# breakout.net
KiCad netlist of a schematic drawn in EAGLE
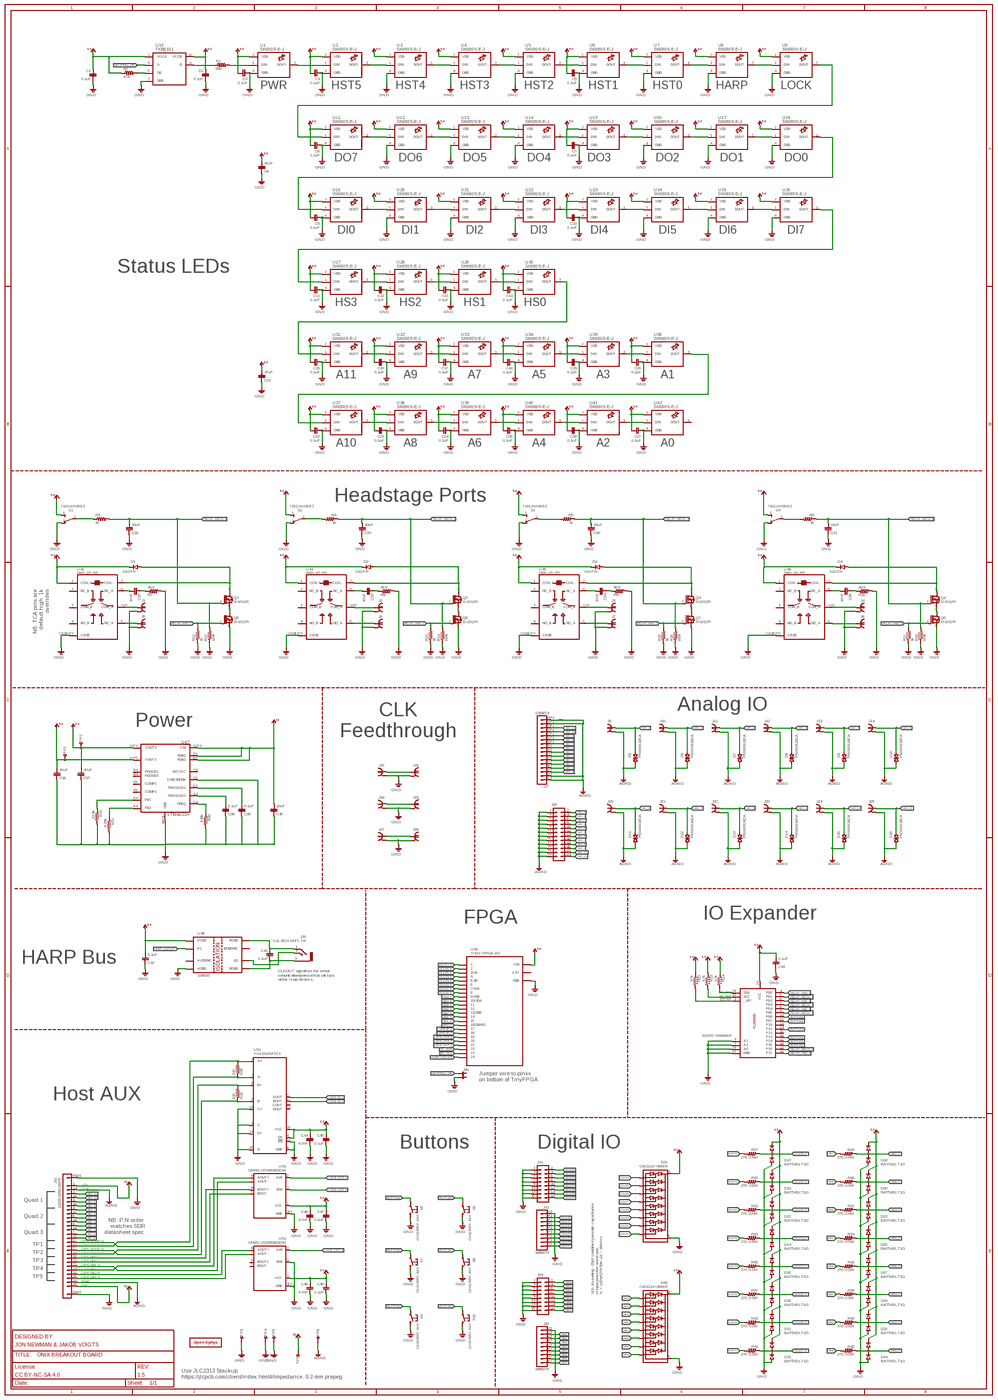
[diagram p0: schematic, sheet 1, overview]
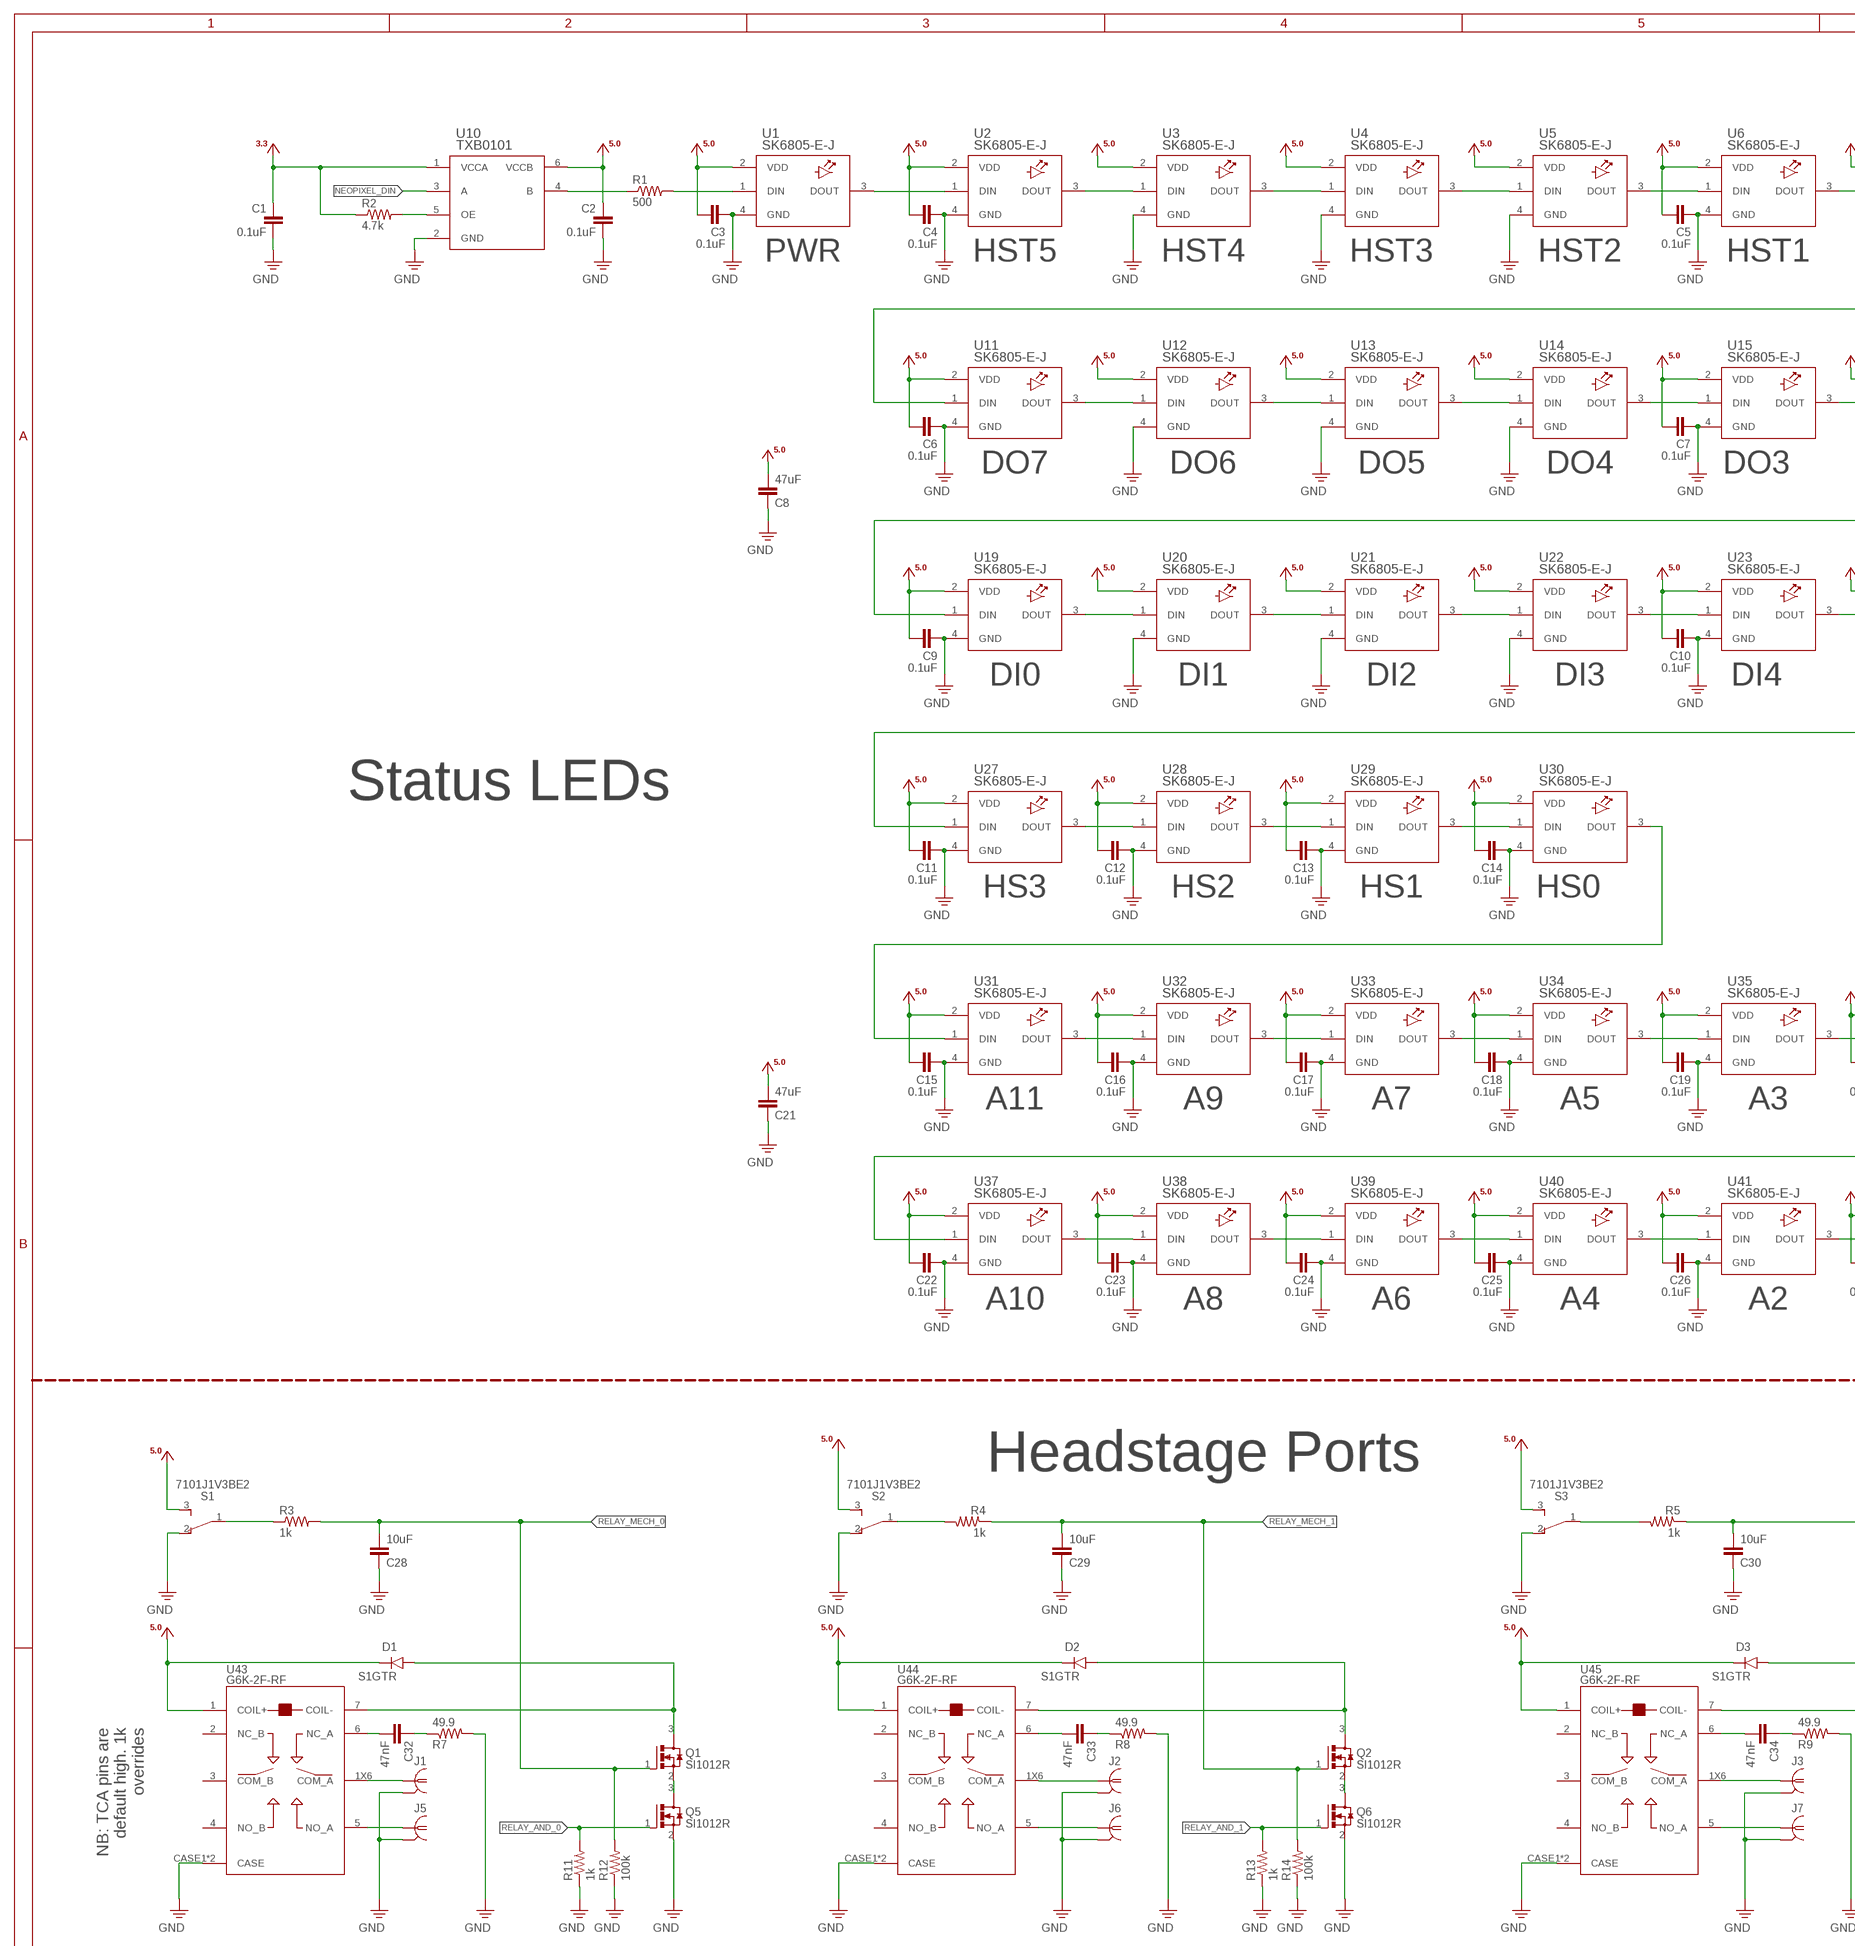
[diagram p1: schematic, sheet 1, part 1 of 4]
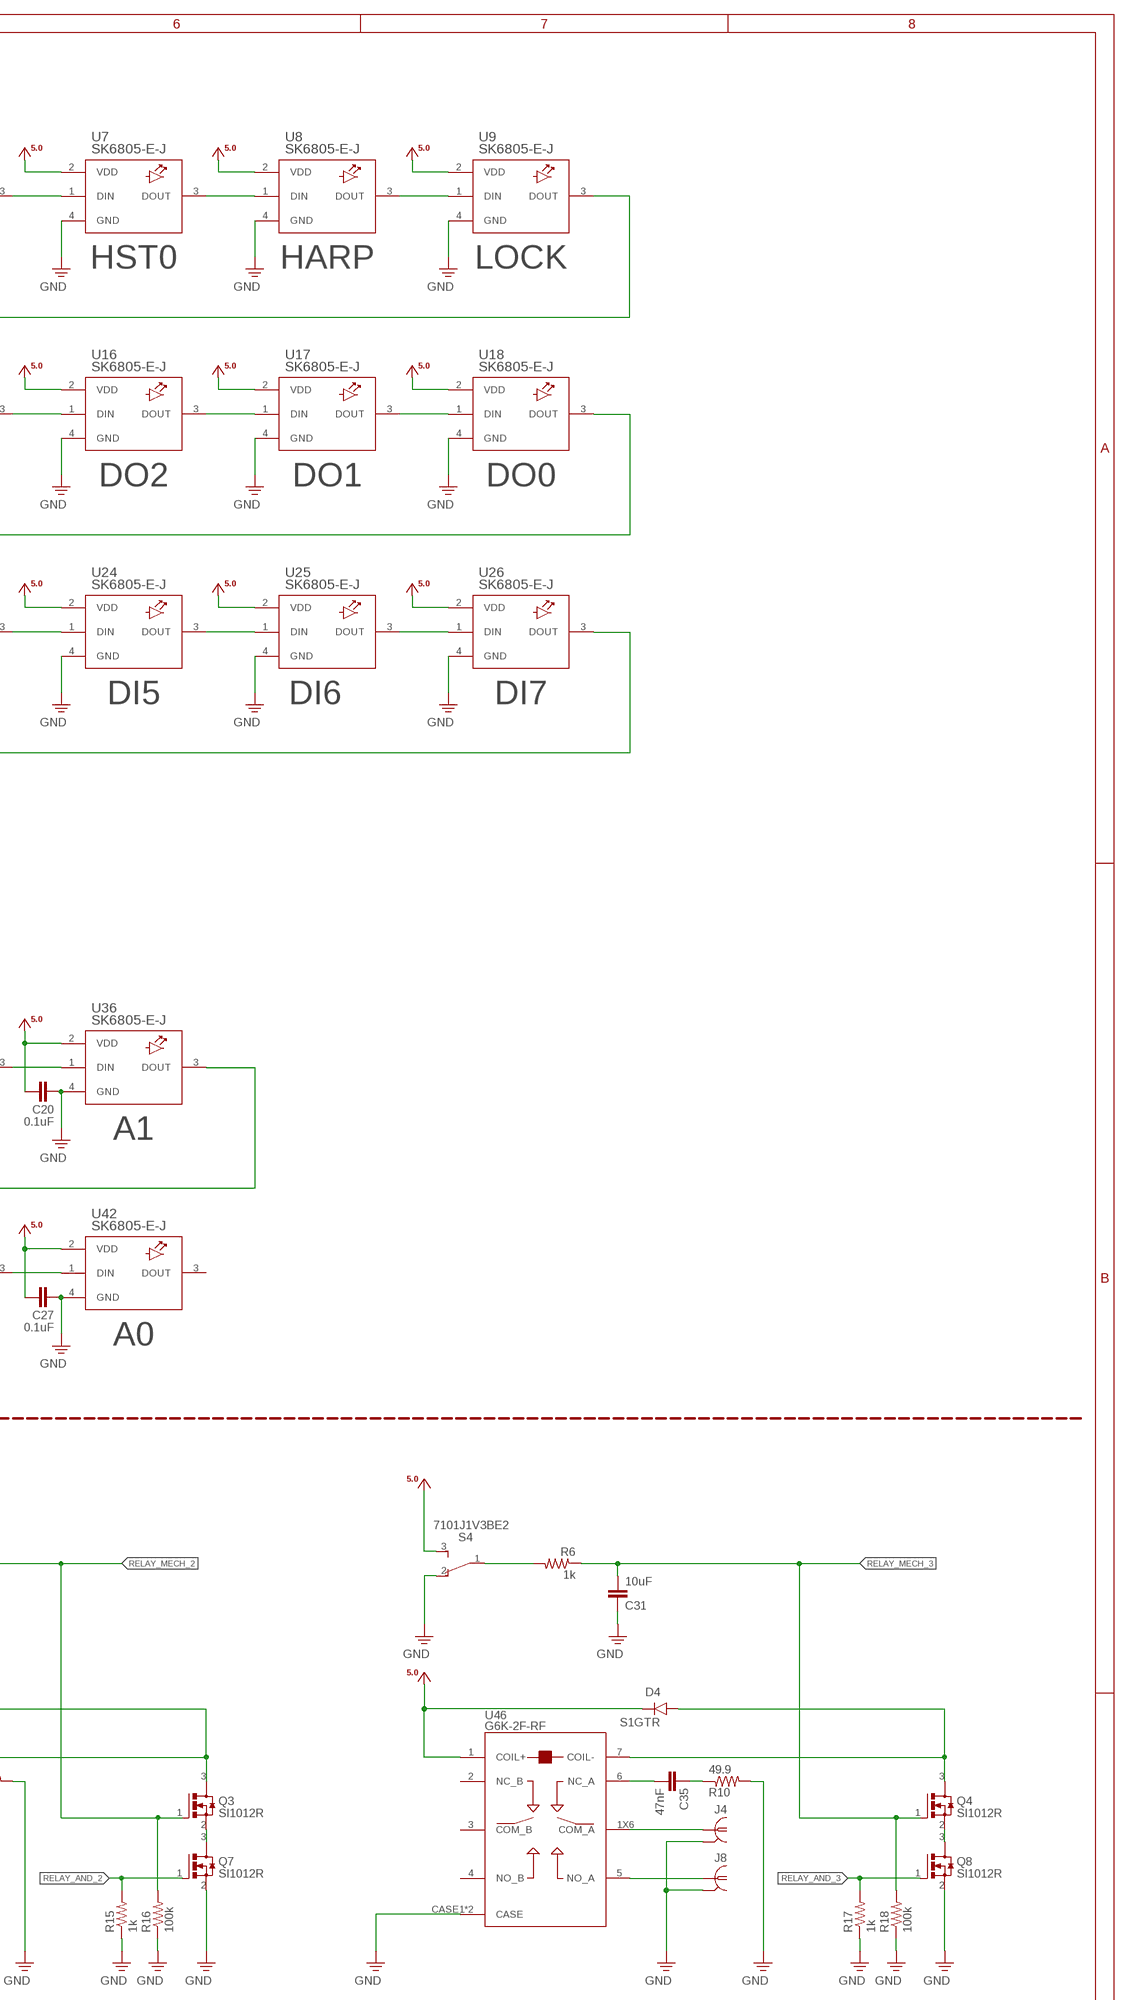
[diagram p2: schematic, sheet 1, part 2 of 4]
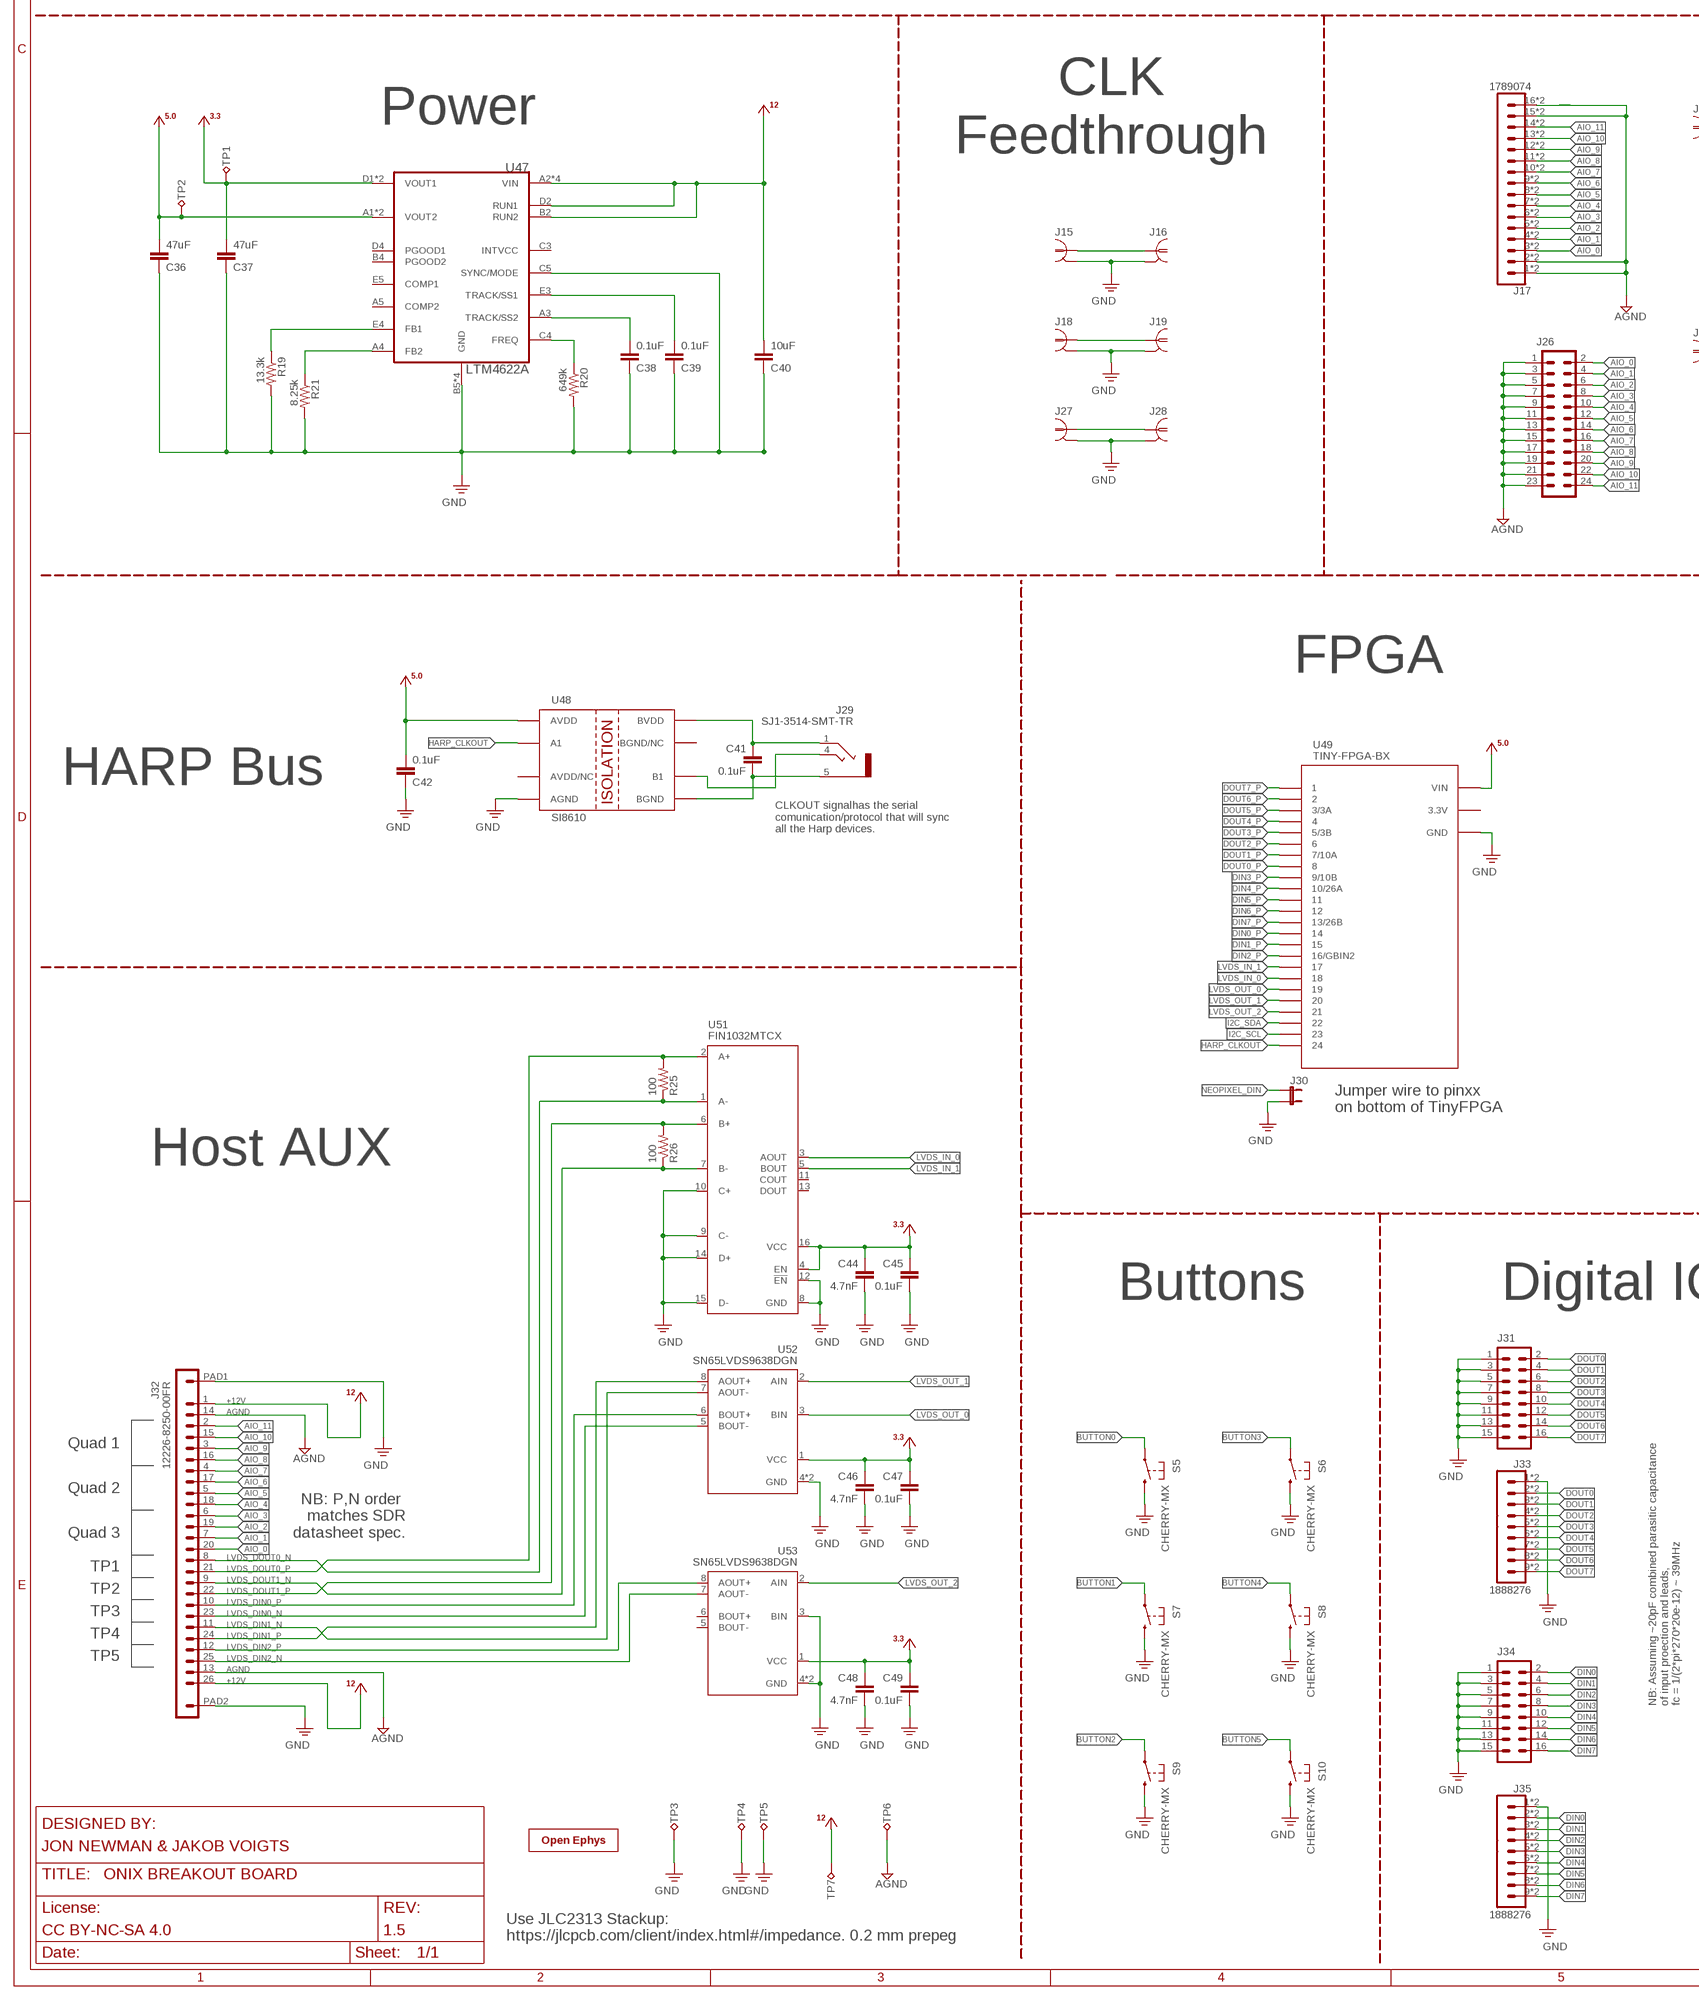
[diagram p3: schematic, sheet 1, part 3 of 4]
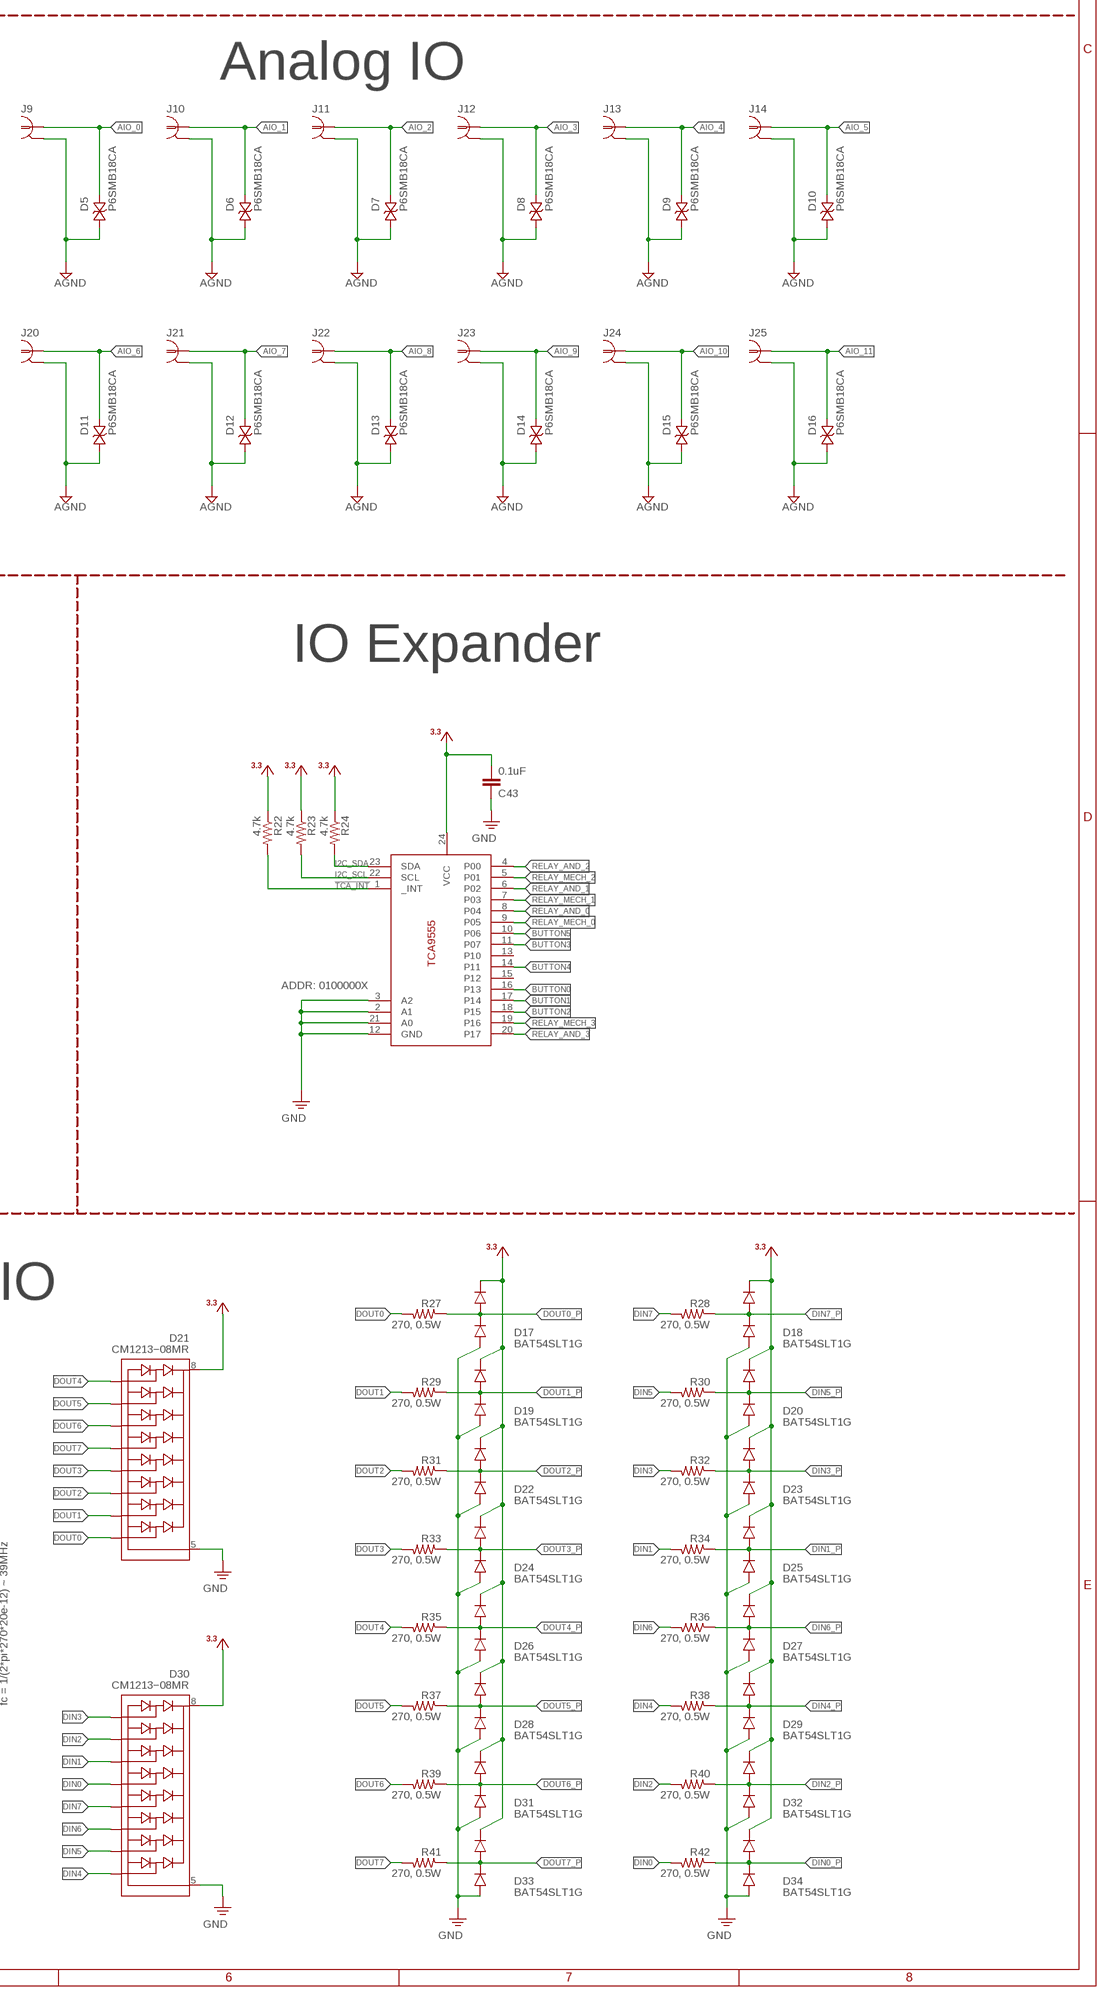
[diagram p4: schematic, sheet 1, part 4 of 4]

(export (version "E")
  (design (tool "Eeschema 10.0.6"))
  (components
    (comp (ref "C1")
      (value "0.1uF")
      (footprint "eagle-import:0402")
      (libsource (lib "eagle-import") (part "C_0402"))
    )
    (comp (ref "C2")
      (value "0.1uF")
      (footprint "eagle-import:0402")
      (libsource (lib "eagle-import") (part "C_0402"))
    )
    (comp (ref "C3")
      (value "0.1uF")
      (footprint "eagle-import:0402")
      (libsource (lib "eagle-import") (part "C_0402"))
    )
    (comp (ref "C4")
      (value "0.1uF")
      (footprint "eagle-import:0402")
      (libsource (lib "eagle-import") (part "C_0402"))
    )
    (comp (ref "C5")
      (value "0.1uF")
      (footprint "eagle-import:0402")
      (libsource (lib "eagle-import") (part "C_0402"))
    )
    (comp (ref "C6")
      (value "0.1uF")
      (footprint "eagle-import:0402")
      (libsource (lib "eagle-import") (part "C_0402"))
    )
    (comp (ref "C7")
      (value "0.1uF")
      (footprint "eagle-import:0402")
      (libsource (lib "eagle-import") (part "C_0402"))
    )
    (comp (ref "C8")
      (value "47uF")
      (footprint "eagle-import:1210")
      (libsource (lib "eagle-import") (part "C_1210"))
    )
    (comp (ref "C9")
      (value "0.1uF")
      (footprint "eagle-import:0402")
      (libsource (lib "eagle-import") (part "C_0402"))
    )
    (comp (ref "C10")
      (value "0.1uF")
      (footprint "eagle-import:0402")
      (libsource (lib "eagle-import") (part "C_0402"))
    )
    (comp (ref "C11")
      (value "0.1uF")
      (footprint "eagle-import:0402")
      (libsource (lib "eagle-import") (part "C_0402"))
    )
    (comp (ref "C12")
      (value "0.1uF")
      (footprint "eagle-import:0402")
      (libsource (lib "eagle-import") (part "C_0402"))
    )
    (comp (ref "C13")
      (value "0.1uF")
      (footprint "eagle-import:0402")
      (libsource (lib "eagle-import") (part "C_0402"))
    )
    (comp (ref "C14")
      (value "0.1uF")
      (footprint "eagle-import:0402")
      (libsource (lib "eagle-import") (part "C_0402"))
    )
    (comp (ref "C15")
      (value "0.1uF")
      (footprint "eagle-import:0402")
      (libsource (lib "eagle-import") (part "C_0402"))
    )
    (comp (ref "C16")
      (value "0.1uF")
      (footprint "eagle-import:0402")
      (libsource (lib "eagle-import") (part "C_0402"))
    )
    (comp (ref "C17")
      (value "0.1uF")
      (footprint "eagle-import:0402")
      (libsource (lib "eagle-import") (part "C_0402"))
    )
    (comp (ref "C18")
      (value "0.1uF")
      (footprint "eagle-import:0402")
      (libsource (lib "eagle-import") (part "C_0402"))
    )
    (comp (ref "C19")
      (value "0.1uF")
      (footprint "eagle-import:0402")
      (libsource (lib "eagle-import") (part "C_0402"))
    )
    (comp (ref "C20")
      (value "0.1uF")
      (footprint "eagle-import:0402")
      (libsource (lib "eagle-import") (part "C_0402"))
    )
    (comp (ref "C21")
      (value "47uF")
      (footprint "eagle-import:1210")
      (libsource (lib "eagle-import") (part "C_1210"))
    )
    (comp (ref "C22")
      (value "0.1uF")
      (footprint "eagle-import:0402")
      (libsource (lib "eagle-import") (part "C_0402"))
    )
    (comp (ref "C23")
      (value "0.1uF")
      (footprint "eagle-import:0402")
      (libsource (lib "eagle-import") (part "C_0402"))
    )
    (comp (ref "C24")
      (value "0.1uF")
      (footprint "eagle-import:0402")
      (libsource (lib "eagle-import") (part "C_0402"))
    )
    (comp (ref "C25")
      (value "0.1uF")
      (footprint "eagle-import:0402")
      (libsource (lib "eagle-import") (part "C_0402"))
    )
    (comp (ref "C26")
      (value "0.1uF")
      (footprint "eagle-import:0402")
      (libsource (lib "eagle-import") (part "C_0402"))
    )
    (comp (ref "C27")
      (value "0.1uF")
      (footprint "eagle-import:0402")
      (libsource (lib "eagle-import") (part "C_0402"))
    )
    (comp (ref "C28")
      (value "10uF")
      (footprint "eagle-import:0805")
      (fields (field (name "PARTNO") "C2012X5R1Cxxxxxxx"))
      (libsource (lib "eagle-import") (part "C_0805"))
    )
    (comp (ref "C29")
      (value "10uF")
      (footprint "eagle-import:0805")
      (fields (field (name "PARTNO") "C2012X5R1Cxxxxxxx"))
      (libsource (lib "eagle-import") (part "C_0805"))
    )
    (comp (ref "C30")
      (value "10uF")
      (footprint "eagle-import:0805")
      (fields (field (name "PARTNO") "C2012X5R1Cxxxxxxx"))
      (libsource (lib "eagle-import") (part "C_0805"))
    )
    (comp (ref "C31")
      (value "10uF")
      (footprint "eagle-import:0805")
      (fields (field (name "PARTNO") "C2012X5R1Cxxxxxxx"))
      (libsource (lib "eagle-import") (part "C_0805"))
    )
    (comp (ref "C32")
      (value "47nF")
      (footprint "eagle-import:0402")
      (libsource (lib "eagle-import") (part "C_0402"))
    )
    (comp (ref "C33")
      (value "47nF")
      (footprint "eagle-import:0402")
      (libsource (lib "eagle-import") (part "C_0402"))
    )
    (comp (ref "C34")
      (value "47nF")
      (footprint "eagle-import:0402")
      (libsource (lib "eagle-import") (part "C_0402"))
    )
    (comp (ref "C35")
      (value "47nF")
      (footprint "eagle-import:0402")
      (libsource (lib "eagle-import") (part "C_0402"))
    )
    (comp (ref "C36")
      (value "47uF")
      (footprint "eagle-import:1210")
      (libsource (lib "eagle-import") (part "C_1210"))
    )
    (comp (ref "C37")
      (value "47uF")
      (footprint "eagle-import:1210")
      (libsource (lib "eagle-import") (part "C_1210"))
    )
    (comp (ref "C38")
      (value "0.1uF")
      (footprint "eagle-import:0402")
      (libsource (lib "eagle-import") (part "C_0402"))
    )
    (comp (ref "C39")
      (value "0.1uF")
      (footprint "eagle-import:0402")
      (libsource (lib "eagle-import") (part "C_0402"))
    )
    (comp (ref "C40")
      (value "10uF")
      (footprint "eagle-import:0805")
      (fields (field (name "PARTNO") "C2012X5R1Cxxxxxxx"))
      (libsource (lib "eagle-import") (part "C_0805"))
    )
    (comp (ref "C41")
      (value "0.1uF")
      (footprint "eagle-import:0402")
      (libsource (lib "eagle-import") (part "C_0402"))
    )
    (comp (ref "C42")
      (value "0.1uF")
      (footprint "eagle-import:0402")
      (libsource (lib "eagle-import") (part "C_0402"))
    )
    (comp (ref "C43")
      (value "0.1uF")
      (footprint "eagle-import:0402")
      (libsource (lib "eagle-import") (part "C_0402"))
    )
    (comp (ref "C44")
      (value "4.7nF")
      (footprint "eagle-import:0402")
      (libsource (lib "eagle-import") (part "C_0402"))
    )
    (comp (ref "C45")
      (value "0.1uF")
      (footprint "eagle-import:0402")
      (libsource (lib "eagle-import") (part "C_0402"))
    )
    (comp (ref "C46")
      (value "4.7nF")
      (footprint "eagle-import:0402")
      (libsource (lib "eagle-import") (part "C_0402"))
    )
    (comp (ref "C47")
      (value "0.1uF")
      (footprint "eagle-import:0402")
      (libsource (lib "eagle-import") (part "C_0402"))
    )
    (comp (ref "C48")
      (value "4.7nF")
      (footprint "eagle-import:0402")
      (libsource (lib "eagle-import") (part "C_0402"))
    )
    (comp (ref "C49")
      (value "0.1uF")
      (footprint "eagle-import:0402")
      (libsource (lib "eagle-import") (part "C_0402"))
    )
    (comp (ref "D1")
      (value "S1GTR")
      (footprint "eagle-import:SMA-DO214AC")
      (libsource (lib "eagle-import") (part "DIODE_S1B-13-F"))
    )
    (comp (ref "D2")
      (value "S1GTR")
      (footprint "eagle-import:SMA-DO214AC")
      (libsource (lib "eagle-import") (part "DIODE_S1B-13-F"))
    )
    (comp (ref "D3")
      (value "S1GTR")
      (footprint "eagle-import:SMA-DO214AC")
      (libsource (lib "eagle-import") (part "DIODE_S1B-13-F"))
    )
    (comp (ref "D4")
      (value "S1GTR")
      (footprint "eagle-import:SMA-DO214AC")
      (libsource (lib "eagle-import") (part "DIODE_S1B-13-F"))
    )
    (comp (ref "D5")
      (value "P6SMB18CA")
      (footprint "eagle-import:SMA-DO214AC")
      (libsource (lib "eagle-import") (part "TVS-DIODE-BI_DO214"))
    )
    (comp (ref "D6")
      (value "P6SMB18CA")
      (footprint "eagle-import:SMA-DO214AC")
      (libsource (lib "eagle-import") (part "TVS-DIODE-BI_DO214"))
    )
    (comp (ref "D7")
      (value "P6SMB18CA")
      (footprint "eagle-import:SMA-DO214AC")
      (libsource (lib "eagle-import") (part "TVS-DIODE-BI_DO214"))
    )
    (comp (ref "D8")
      (value "P6SMB18CA")
      (footprint "eagle-import:SMA-DO214AC")
      (libsource (lib "eagle-import") (part "TVS-DIODE-BI_DO214"))
    )
    (comp (ref "D9")
      (value "P6SMB18CA")
      (footprint "eagle-import:SMA-DO214AC")
      (libsource (lib "eagle-import") (part "TVS-DIODE-BI_DO214"))
    )
    (comp (ref "D10")
      (value "P6SMB18CA")
      (footprint "eagle-import:SMA-DO214AC")
      (libsource (lib "eagle-import") (part "TVS-DIODE-BI_DO214"))
    )
    (comp (ref "D11")
      (value "P6SMB18CA")
      (footprint "eagle-import:SMA-DO214AC")
      (libsource (lib "eagle-import") (part "TVS-DIODE-BI_DO214"))
    )
    (comp (ref "D12")
      (value "P6SMB18CA")
      (footprint "eagle-import:SMA-DO214AC")
      (libsource (lib "eagle-import") (part "TVS-DIODE-BI_DO214"))
    )
    (comp (ref "D13")
      (value "P6SMB18CA")
      (footprint "eagle-import:SMA-DO214AC")
      (libsource (lib "eagle-import") (part "TVS-DIODE-BI_DO214"))
    )
    (comp (ref "D14")
      (value "P6SMB18CA")
      (footprint "eagle-import:SMA-DO214AC")
      (libsource (lib "eagle-import") (part "TVS-DIODE-BI_DO214"))
    )
    (comp (ref "D15")
      (value "P6SMB18CA")
      (footprint "eagle-import:SMA-DO214AC")
      (libsource (lib "eagle-import") (part "TVS-DIODE-BI_DO214"))
    )
    (comp (ref "D16")
      (value "P6SMB18CA")
      (footprint "eagle-import:SMA-DO214AC")
      (libsource (lib "eagle-import") (part "TVS-DIODE-BI_DO214"))
    )
    (comp (ref "D17")
      (value "BAT54SLT1G")
      (footprint "eagle-import:SOT23")
      (libsource (lib "eagle-import") (part "DIODE2_SOT23"))
    )
    (comp (ref "D18")
      (value "BAT54SLT1G")
      (footprint "eagle-import:SOT23")
      (libsource (lib "eagle-import") (part "DIODE2_SOT23"))
    )
    (comp (ref "D19")
      (value "BAT54SLT1G")
      (footprint "eagle-import:SOT23")
      (libsource (lib "eagle-import") (part "DIODE2_SOT23"))
    )
    (comp (ref "D20")
      (value "BAT54SLT1G")
      (footprint "eagle-import:SOT23")
      (libsource (lib "eagle-import") (part "DIODE2_SOT23"))
    )
    (comp (ref "D21")
      (value "CM1213−08MR")
      (footprint "eagle-import:MSOP-10-3X3")
      (libsource (lib "eagle-import") (part "TVS-DIODE-BI-8_MSOP"))
    )
    (comp (ref "D22")
      (value "BAT54SLT1G")
      (footprint "eagle-import:SOT23")
      (libsource (lib "eagle-import") (part "DIODE2_SOT23"))
    )
    (comp (ref "D23")
      (value "BAT54SLT1G")
      (footprint "eagle-import:SOT23")
      (libsource (lib "eagle-import") (part "DIODE2_SOT23"))
    )
    (comp (ref "D24")
      (value "BAT54SLT1G")
      (footprint "eagle-import:SOT23")
      (libsource (lib "eagle-import") (part "DIODE2_SOT23"))
    )
    (comp (ref "D25")
      (value "BAT54SLT1G")
      (footprint "eagle-import:SOT23")
      (libsource (lib "eagle-import") (part "DIODE2_SOT23"))
    )
    (comp (ref "D26")
      (value "BAT54SLT1G")
      (footprint "eagle-import:SOT23")
      (libsource (lib "eagle-import") (part "DIODE2_SOT23"))
    )
    (comp (ref "D27")
      (value "BAT54SLT1G")
      (footprint "eagle-import:SOT23")
      (libsource (lib "eagle-import") (part "DIODE2_SOT23"))
    )
    (comp (ref "D28")
      (value "BAT54SLT1G")
      (footprint "eagle-import:SOT23")
      (libsource (lib "eagle-import") (part "DIODE2_SOT23"))
    )
    (comp (ref "D29")
      (value "BAT54SLT1G")
      (footprint "eagle-import:SOT23")
      (libsource (lib "eagle-import") (part "DIODE2_SOT23"))
    )
    (comp (ref "D30")
      (value "CM1213−08MR")
      (footprint "eagle-import:MSOP-10-3X3")
      (libsource (lib "eagle-import") (part "TVS-DIODE-BI-8_MSOP"))
    )
    (comp (ref "D31")
      (value "BAT54SLT1G")
      (footprint "eagle-import:SOT23")
      (libsource (lib "eagle-import") (part "DIODE2_SOT23"))
    )
    (comp (ref "D32")
      (value "BAT54SLT1G")
      (footprint "eagle-import:SOT23")
      (libsource (lib "eagle-import") (part "DIODE2_SOT23"))
    )
    (comp (ref "D33")
      (value "BAT54SLT1G")
      (footprint "eagle-import:SOT23")
      (libsource (lib "eagle-import") (part "DIODE2_SOT23"))
    )
    (comp (ref "D34")
      (value "BAT54SLT1G")
      (footprint "eagle-import:SOT23")
      (libsource (lib "eagle-import") (part "DIODE2_SOT23"))
    )
    (comp (ref "J1")
      (value "COAX_SMA-VERT")
      (footprint "eagle-import:SMA_JACK_142-0701-201")
      (libsource (lib "eagle-import") (part "COAX_SMA-VERT"))
    )
    (comp (ref "J2")
      (value "COAX_SMA-VERT")
      (footprint "eagle-import:SMA_JACK_142-0701-201")
      (libsource (lib "eagle-import") (part "COAX_SMA-VERT"))
    )
    (comp (ref "J3")
      (value "COAX_SMA-VERT")
      (footprint "eagle-import:SMA_JACK_142-0701-201")
      (libsource (lib "eagle-import") (part "COAX_SMA-VERT"))
    )
    (comp (ref "J4")
      (value "COAX_SMA-VERT")
      (footprint "eagle-import:SMA_JACK_142-0701-201")
      (libsource (lib "eagle-import") (part "COAX_SMA-VERT"))
    )
    (comp (ref "J5")
      (value "COAX_MMCX-THRU")
      (footprint "eagle-import:MMCX-THRU")
      (libsource (lib "eagle-import") (part "COAX_MMCX-THRU"))
    )
    (comp (ref "J6")
      (value "COAX_MMCX-THRU")
      (footprint "eagle-import:MMCX-THRU")
      (libsource (lib "eagle-import") (part "COAX_MMCX-THRU"))
    )
    (comp (ref "J7")
      (value "COAX_MMCX-THRU")
      (footprint "eagle-import:MMCX-THRU")
      (libsource (lib "eagle-import") (part "COAX_MMCX-THRU"))
    )
    (comp (ref "J8")
      (value "COAX_MMCX-THRU")
      (footprint "eagle-import:MMCX-THRU")
      (libsource (lib "eagle-import") (part "COAX_MMCX-THRU"))
    )
    (comp (ref "J9")
      (value "COAX_0731010360")
      (footprint "eagle-import:0731010360")
      (libsource (lib "eagle-import") (part "COAX_0731010360"))
    )
    (comp (ref "J10")
      (value "COAX_0731010360")
      (footprint "eagle-import:0731010360")
      (libsource (lib "eagle-import") (part "COAX_0731010360"))
    )
    (comp (ref "J11")
      (value "COAX_0731010360")
      (footprint "eagle-import:0731010360")
      (libsource (lib "eagle-import") (part "COAX_0731010360"))
    )
    (comp (ref "J12")
      (value "COAX_0731010360")
      (footprint "eagle-import:0731010360")
      (libsource (lib "eagle-import") (part "COAX_0731010360"))
    )
    (comp (ref "J13")
      (value "COAX_0731010360")
      (footprint "eagle-import:0731010360")
      (libsource (lib "eagle-import") (part "COAX_0731010360"))
    )
    (comp (ref "J14")
      (value "COAX_0731010360")
      (footprint "eagle-import:0731010360")
      (libsource (lib "eagle-import") (part "COAX_0731010360"))
    )
    (comp (ref "J15")
      (value "COAX_MMCX-THRU")
      (footprint "eagle-import:MMCX-THRU")
      (libsource (lib "eagle-import") (part "COAX_MMCX-THRU"))
    )
    (comp (ref "J16")
      (value "COAX_SMA-VERT")
      (footprint "eagle-import:SMA_JACK_142-0701-201")
      (libsource (lib "eagle-import") (part "COAX_SMA-VERT"))
    )
    (comp (ref "J17")
      (value "1789074")
      (footprint "eagle-import:SCREW16-2")
      (libsource (lib "eagle-import") (part "PINHD-1X16"))
    )
    (comp (ref "J18")
      (value "COAX_MMCX-THRU")
      (footprint "eagle-import:MMCX-THRU")
      (libsource (lib "eagle-import") (part "COAX_MMCX-THRU"))
    )
    (comp (ref "J19")
      (value "COAX_SMA-VERT")
      (footprint "eagle-import:SMA_JACK_142-0701-201")
      (libsource (lib "eagle-import") (part "COAX_SMA-VERT"))
    )
    (comp (ref "J20")
      (value "COAX_0731010360")
      (footprint "eagle-import:0731010360")
      (libsource (lib "eagle-import") (part "COAX_0731010360"))
    )
    (comp (ref "J21")
      (value "COAX_0731010360")
      (footprint "eagle-import:0731010360")
      (libsource (lib "eagle-import") (part "COAX_0731010360"))
    )
    (comp (ref "J22")
      (value "COAX_0731010360")
      (footprint "eagle-import:0731010360")
      (libsource (lib "eagle-import") (part "COAX_0731010360"))
    )
    (comp (ref "J23")
      (value "COAX_0731010360")
      (footprint "eagle-import:0731010360")
      (libsource (lib "eagle-import") (part "COAX_0731010360"))
    )
    (comp (ref "J24")
      (value "COAX_0731010360")
      (footprint "eagle-import:0731010360")
      (libsource (lib "eagle-import") (part "COAX_0731010360"))
    )
    (comp (ref "J25")
      (value "COAX_0731010360")
      (footprint "eagle-import:0731010360")
      (libsource (lib "eagle-import") (part "COAX_0731010360"))
    )
    (comp (ref "J26")
      (value "69168-124HLF")
      (footprint "eagle-import:2X12-BIG")
      (libsource (lib "eagle-import") (part "PINHD-2X12_0.1{dblquote}"))
    )
    (comp (ref "J27")
      (value "COAX_MMCX-THRU")
      (footprint "eagle-import:MMCX-THRU")
      (libsource (lib "eagle-import") (part "COAX_MMCX-THRU"))
    )
    (comp (ref "J28")
      (value "COAX_SMA-VERT")
      (footprint "eagle-import:SMA_JACK_142-0701-201")
      (libsource (lib "eagle-import") (part "COAX_SMA-VERT"))
    )
    (comp (ref "J29")
      (value "SJ1-3514-SMT-TR")
      (footprint "eagle-import:35RASMT2BHNTRX")
      (libsource (lib "eagle-import") (part "STEREO_JACK"))
    )
    (comp (ref "J30")
      (value "JP2E_THRU-HOLE")
      (footprint "eagle-import:JP2")
      (libsource (lib "eagle-import") (part "JP2E_THRU-HOLE"))
    )
    (comp (ref "J31")
      (value "69168-116HLF")
      (footprint "eagle-import:2X08-BIG")
      (libsource (lib "eagle-import") (part "PINHD-2X8_THRU"))
    )
    (comp (ref "J32")
      (value "12226-8250-00FR")
      (footprint "eagle-import:12226-82X0-00XX")
      (libsource (lib "eagle-import") (part "PINHD-1X26_122"))
    )
    (comp (ref "J33")
      (value "1888276")
      (footprint "eagle-import:SCREW9-2")
      (libsource (lib "eagle-import") (part "PINHD-1X9_SCREW2"))
    )
    (comp (ref "J34")
      (value "69168-116HLF")
      (footprint "eagle-import:2X08-BIG")
      (libsource (lib "eagle-import") (part "PINHD-2X8_THRU"))
    )
    (comp (ref "J35")
      (value "1888276")
      (footprint "eagle-import:SCREW9-2")
      (libsource (lib "eagle-import") (part "PINHD-1X9_SCREW2"))
    )
    (comp (ref "Q1")
      (value "SI1012R")
      (footprint "eagle-import:SC75")
      (libsource (lib "eagle-import") (part "N-MOSFET_SC75-GSD"))
    )
    (comp (ref "Q2")
      (value "SI1012R")
      (footprint "eagle-import:SC75")
      (libsource (lib "eagle-import") (part "N-MOSFET_SC75-GSD"))
    )
    (comp (ref "Q3")
      (value "SI1012R")
      (footprint "eagle-import:SC75")
      (libsource (lib "eagle-import") (part "N-MOSFET_SC75-GSD"))
    )
    (comp (ref "Q4")
      (value "SI1012R")
      (footprint "eagle-import:SC75")
      (libsource (lib "eagle-import") (part "N-MOSFET_SC75-GSD"))
    )
    (comp (ref "Q5")
      (value "SI1012R")
      (footprint "eagle-import:SC75")
      (libsource (lib "eagle-import") (part "N-MOSFET_SC75-GSD"))
    )
    (comp (ref "Q6")
      (value "SI1012R")
      (footprint "eagle-import:SC75")
      (libsource (lib "eagle-import") (part "N-MOSFET_SC75-GSD"))
    )
    (comp (ref "Q7")
      (value "SI1012R")
      (footprint "eagle-import:SC75")
      (libsource (lib "eagle-import") (part "N-MOSFET_SC75-GSD"))
    )
    (comp (ref "Q8")
      (value "SI1012R")
      (footprint "eagle-import:SC75")
      (libsource (lib "eagle-import") (part "N-MOSFET_SC75-GSD"))
    )
    (comp (ref "R1")
      (value "500")
      (footprint "eagle-import:0402")
      (libsource (lib "eagle-import") (part "R_0402"))
    )
    (comp (ref "R2")
      (value "4.7k")
      (footprint "eagle-import:0402")
      (libsource (lib "eagle-import") (part "R_0402"))
    )
    (comp (ref "R3")
      (value "1k")
      (footprint "eagle-import:0402")
      (libsource (lib "eagle-import") (part "R_0402"))
    )
    (comp (ref "R4")
      (value "1k")
      (footprint "eagle-import:0402")
      (libsource (lib "eagle-import") (part "R_0402"))
    )
    (comp (ref "R5")
      (value "1k")
      (footprint "eagle-import:0402")
      (libsource (lib "eagle-import") (part "R_0402"))
    )
    (comp (ref "R6")
      (value "1k")
      (footprint "eagle-import:0402")
      (libsource (lib "eagle-import") (part "R_0402"))
    )
    (comp (ref "R7")
      (value "49.9")
      (footprint "eagle-import:0402")
      (libsource (lib "eagle-import") (part "R_0402"))
    )
    (comp (ref "R8")
      (value "49.9")
      (footprint "eagle-import:0402")
      (libsource (lib "eagle-import") (part "R_0402"))
    )
    (comp (ref "R9")
      (value "49.9")
      (footprint "eagle-import:0402")
      (libsource (lib "eagle-import") (part "R_0402"))
    )
    (comp (ref "R10")
      (value "49.9")
      (footprint "eagle-import:0402")
      (libsource (lib "eagle-import") (part "R_0402"))
    )
    (comp (ref "R11")
      (value "1k")
      (footprint "eagle-import:0402")
      (libsource (lib "eagle-import") (part "R_0402"))
    )
    (comp (ref "R12")
      (value "100k")
      (footprint "eagle-import:0402")
      (libsource (lib "eagle-import") (part "R_0402"))
    )
    (comp (ref "R13")
      (value "1k")
      (footprint "eagle-import:0402")
      (libsource (lib "eagle-import") (part "R_0402"))
    )
    (comp (ref "R14")
      (value "100k")
      (footprint "eagle-import:0402")
      (libsource (lib "eagle-import") (part "R_0402"))
    )
    (comp (ref "R15")
      (value "1k")
      (footprint "eagle-import:0402")
      (libsource (lib "eagle-import") (part "R_0402"))
    )
    (comp (ref "R16")
      (value "100k")
      (footprint "eagle-import:0402")
      (libsource (lib "eagle-import") (part "R_0402"))
    )
    (comp (ref "R17")
      (value "1k")
      (footprint "eagle-import:0402")
      (libsource (lib "eagle-import") (part "R_0402"))
    )
    (comp (ref "R18")
      (value "100k")
      (footprint "eagle-import:0402")
      (libsource (lib "eagle-import") (part "R_0402"))
    )
    (comp (ref "R19")
      (value "13.3k")
      (footprint "eagle-import:0402")
      (libsource (lib "eagle-import") (part "R_0402"))
    )
    (comp (ref "R20")
      (value "649k")
      (footprint "eagle-import:0402")
      (libsource (lib "eagle-import") (part "R_0402"))
    )
    (comp (ref "R21")
      (value "8.25k")
      (footprint "eagle-import:0402")
      (libsource (lib "eagle-import") (part "R_0402"))
    )
    (comp (ref "R22")
      (value "4.7k")
      (footprint "eagle-import:0402")
      (libsource (lib "eagle-import") (part "R_0402"))
    )
    (comp (ref "R23")
      (value "4.7k")
      (footprint "eagle-import:0402")
      (libsource (lib "eagle-import") (part "R_0402"))
    )
    (comp (ref "R24")
      (value "4.7k")
      (footprint "eagle-import:0402")
      (libsource (lib "eagle-import") (part "R_0402"))
    )
    (comp (ref "R25")
      (value "100")
      (footprint "eagle-import:0402")
      (libsource (lib "eagle-import") (part "R_0402"))
    )
    (comp (ref "R26")
      (value "100")
      (footprint "eagle-import:0402")
      (libsource (lib "eagle-import") (part "R_0402"))
    )
    (comp (ref "R27")
      (value "270, 0.5W")
      (footprint "eagle-import:0805")
      (libsource (lib "eagle-import") (part "R_0805"))
    )
    (comp (ref "R28")
      (value "270, 0.5W")
      (footprint "eagle-import:0805")
      (libsource (lib "eagle-import") (part "R_0805"))
    )
    (comp (ref "R29")
      (value "270, 0.5W")
      (footprint "eagle-import:0805")
      (libsource (lib "eagle-import") (part "R_0805"))
    )
    (comp (ref "R30")
      (value "270, 0.5W")
      (footprint "eagle-import:0805")
      (libsource (lib "eagle-import") (part "R_0805"))
    )
    (comp (ref "R31")
      (value "270, 0.5W")
      (footprint "eagle-import:0805")
      (libsource (lib "eagle-import") (part "R_0805"))
    )
    (comp (ref "R32")
      (value "270, 0.5W")
      (footprint "eagle-import:0805")
      (libsource (lib "eagle-import") (part "R_0805"))
    )
    (comp (ref "R33")
      (value "270, 0.5W")
      (footprint "eagle-import:0805")
      (libsource (lib "eagle-import") (part "R_0805"))
    )
    (comp (ref "R34")
      (value "270, 0.5W")
      (footprint "eagle-import:0805")
      (libsource (lib "eagle-import") (part "R_0805"))
    )
    (comp (ref "R35")
      (value "270, 0.5W")
      (footprint "eagle-import:0805")
      (libsource (lib "eagle-import") (part "R_0805"))
    )
    (comp (ref "R36")
      (value "270, 0.5W")
      (footprint "eagle-import:0805")
      (libsource (lib "eagle-import") (part "R_0805"))
    )
    (comp (ref "R37")
      (value "270, 0.5W")
      (footprint "eagle-import:0805")
      (libsource (lib "eagle-import") (part "R_0805"))
    )
    (comp (ref "R38")
      (value "270, 0.5W")
      (footprint "eagle-import:0805")
      (libsource (lib "eagle-import") (part "R_0805"))
    )
    (comp (ref "R39")
      (value "270, 0.5W")
      (footprint "eagle-import:0805")
      (libsource (lib "eagle-import") (part "R_0805"))
    )
    (comp (ref "R40")
      (value "270, 0.5W")
      (footprint "eagle-import:0805")
      (libsource (lib "eagle-import") (part "R_0805"))
    )
    (comp (ref "R41")
      (value "270, 0.5W")
      (footprint "eagle-import:0805")
      (libsource (lib "eagle-import") (part "R_0805"))
    )
    (comp (ref "R42")
      (value "270, 0.5W")
      (footprint "eagle-import:0805")
      (libsource (lib "eagle-import") (part "R_0805"))
    )
    (comp (ref "S1")
      (value "7101J1V3BE2")
      (footprint "eagle-import:CK_7101J1V3QE2")
      (libsource (lib "eagle-import") (part "SPDT_CK-710"))
    )
    (comp (ref "S2")
      (value "7101J1V3BE2")
      (footprint "eagle-import:CK_7101J1V3QE2")
      (libsource (lib "eagle-import") (part "SPDT_CK-710"))
    )
    (comp (ref "S3")
      (value "7101J1V3BE2")
      (footprint "eagle-import:CK_7101J1V3QE2")
      (libsource (lib "eagle-import") (part "SPDT_CK-710"))
    )
    (comp (ref "S4")
      (value "7101J1V3BE2")
      (footprint "eagle-import:CK_7101J1V3QE2")
      (libsource (lib "eagle-import") (part "SPDT_CK-710"))
    )
    (comp (ref "S5")
      (value "CHERRY-MX")
      (footprint "eagle-import:CHERRY-MX")
      (libsource (lib "eagle-import") (part "SPST_TACT2_CHERRY-MX"))
    )
    (comp (ref "S6")
      (value "CHERRY-MX")
      (footprint "eagle-import:CHERRY-MX")
      (libsource (lib "eagle-import") (part "SPST_TACT2_CHERRY-MX"))
    )
    (comp (ref "S7")
      (value "CHERRY-MX")
      (footprint "eagle-import:CHERRY-MX")
      (libsource (lib "eagle-import") (part "SPST_TACT2_CHERRY-MX"))
    )
    (comp (ref "S8")
      (value "CHERRY-MX")
      (footprint "eagle-import:CHERRY-MX")
      (libsource (lib "eagle-import") (part "SPST_TACT2_CHERRY-MX"))
    )
    (comp (ref "S9")
      (value "CHERRY-MX")
      (footprint "eagle-import:CHERRY-MX")
      (libsource (lib "eagle-import") (part "SPST_TACT2_CHERRY-MX"))
    )
    (comp (ref "S10")
      (value "CHERRY-MX")
      (footprint "eagle-import:CHERRY-MX")
      (libsource (lib "eagle-import") (part "SPST_TACT2_CHERRY-MX"))
    )
    (comp (ref "TP1")
      (value "TPTP19R")
      (footprint "eagle-import:TP19R")
      (libsource (lib "eagle-import") (part "TPTP19R"))
    )
    (comp (ref "TP2")
      (value "TPTP19R")
      (footprint "eagle-import:TP19R")
      (libsource (lib "eagle-import") (part "TPTP19R"))
    )
    (comp (ref "TP3")
      (value "TP_2MM")
      (footprint "eagle-import:TESTPOINT_2MM")
      (libsource (lib "eagle-import") (part "TP_2MM"))
    )
    (comp (ref "TP4")
      (value "TP_2MM")
      (footprint "eagle-import:TESTPOINT_2MM")
      (libsource (lib "eagle-import") (part "TP_2MM"))
    )
    (comp (ref "TP5")
      (value "TP_2MM")
      (footprint "eagle-import:TESTPOINT_2MM")
      (libsource (lib "eagle-import") (part "TP_2MM"))
    )
    (comp (ref "TP6")
      (value "TP_2MM")
      (footprint "eagle-import:TESTPOINT_2MM")
      (libsource (lib "eagle-import") (part "TP_2MM"))
    )
    (comp (ref "TP7")
      (value "TP_2MM")
      (footprint "eagle-import:TESTPOINT_2MM")
      (libsource (lib "eagle-import") (part "TP_2MM"))
    )
    (comp (ref "U1")
      (value "SK6805-E-J")
      (footprint "eagle-import:NEOPIXEL-1.5X1.5")
      (libsource (lib "eagle-import") (part "NEOPIXEL_1.5X1.5"))
    )
    (comp (ref "U2")
      (value "SK6805-E-J")
      (footprint "eagle-import:NEOPIXEL-1.5X1.5")
      (libsource (lib "eagle-import") (part "NEOPIXEL_1.5X1.5"))
    )
    (comp (ref "U3")
      (value "SK6805-E-J")
      (footprint "eagle-import:NEOPIXEL-1.5X1.5")
      (libsource (lib "eagle-import") (part "NEOPIXEL_1.5X1.5"))
    )
    (comp (ref "U4")
      (value "SK6805-E-J")
      (footprint "eagle-import:NEOPIXEL-1.5X1.5")
      (libsource (lib "eagle-import") (part "NEOPIXEL_1.5X1.5"))
    )
    (comp (ref "U5")
      (value "SK6805-E-J")
      (footprint "eagle-import:NEOPIXEL-1.5X1.5")
      (libsource (lib "eagle-import") (part "NEOPIXEL_1.5X1.5"))
    )
    (comp (ref "U6")
      (value "SK6805-E-J")
      (footprint "eagle-import:NEOPIXEL-1.5X1.5")
      (libsource (lib "eagle-import") (part "NEOPIXEL_1.5X1.5"))
    )
    (comp (ref "U7")
      (value "SK6805-E-J")
      (footprint "eagle-import:NEOPIXEL-1.5X1.5")
      (libsource (lib "eagle-import") (part "NEOPIXEL_1.5X1.5"))
    )
    (comp (ref "U8")
      (value "SK6805-E-J")
      (footprint "eagle-import:NEOPIXEL-1.5X1.5")
      (libsource (lib "eagle-import") (part "NEOPIXEL_1.5X1.5"))
    )
    (comp (ref "U9")
      (value "SK6805-E-J")
      (footprint "eagle-import:NEOPIXEL-1.5X1.5")
      (libsource (lib "eagle-import") (part "NEOPIXEL_1.5X1.5"))
    )
    (comp (ref "U10")
      (value "TXB0101")
      (footprint "eagle-import:SOT23-6")
      (libsource (lib "eagle-import") (part "LEVEL_SHIFTER_SOT23"))
    )
    (comp (ref "U11")
      (value "SK6805-E-J")
      (footprint "eagle-import:NEOPIXEL-1.5X1.5")
      (libsource (lib "eagle-import") (part "NEOPIXEL_1.5X1.5"))
    )
    (comp (ref "U12")
      (value "SK6805-E-J")
      (footprint "eagle-import:NEOPIXEL-1.5X1.5")
      (libsource (lib "eagle-import") (part "NEOPIXEL_1.5X1.5"))
    )
    (comp (ref "U13")
      (value "SK6805-E-J")
      (footprint "eagle-import:NEOPIXEL-1.5X1.5")
      (libsource (lib "eagle-import") (part "NEOPIXEL_1.5X1.5"))
    )
    (comp (ref "U14")
      (value "SK6805-E-J")
      (footprint "eagle-import:NEOPIXEL-1.5X1.5")
      (libsource (lib "eagle-import") (part "NEOPIXEL_1.5X1.5"))
    )
    (comp (ref "U15")
      (value "SK6805-E-J")
      (footprint "eagle-import:NEOPIXEL-1.5X1.5")
      (libsource (lib "eagle-import") (part "NEOPIXEL_1.5X1.5"))
    )
    (comp (ref "U16")
      (value "SK6805-E-J")
      (footprint "eagle-import:NEOPIXEL-1.5X1.5")
      (libsource (lib "eagle-import") (part "NEOPIXEL_1.5X1.5"))
    )
    (comp (ref "U17")
      (value "SK6805-E-J")
      (footprint "eagle-import:NEOPIXEL-1.5X1.5")
      (libsource (lib "eagle-import") (part "NEOPIXEL_1.5X1.5"))
    )
    (comp (ref "U18")
      (value "SK6805-E-J")
      (footprint "eagle-import:NEOPIXEL-1.5X1.5")
      (libsource (lib "eagle-import") (part "NEOPIXEL_1.5X1.5"))
    )
    (comp (ref "U19")
      (value "SK6805-E-J")
      (footprint "eagle-import:NEOPIXEL-1.5X1.5")
      (libsource (lib "eagle-import") (part "NEOPIXEL_1.5X1.5"))
    )
    (comp (ref "U20")
      (value "SK6805-E-J")
      (footprint "eagle-import:NEOPIXEL-1.5X1.5")
      (libsource (lib "eagle-import") (part "NEOPIXEL_1.5X1.5"))
    )
    (comp (ref "U21")
      (value "SK6805-E-J")
      (footprint "eagle-import:NEOPIXEL-1.5X1.5")
      (libsource (lib "eagle-import") (part "NEOPIXEL_1.5X1.5"))
    )
    (comp (ref "U22")
      (value "SK6805-E-J")
      (footprint "eagle-import:NEOPIXEL-1.5X1.5")
      (libsource (lib "eagle-import") (part "NEOPIXEL_1.5X1.5"))
    )
    (comp (ref "U23")
      (value "SK6805-E-J")
      (footprint "eagle-import:NEOPIXEL-1.5X1.5")
      (libsource (lib "eagle-import") (part "NEOPIXEL_1.5X1.5"))
    )
    (comp (ref "U24")
      (value "SK6805-E-J")
      (footprint "eagle-import:NEOPIXEL-1.5X1.5")
      (libsource (lib "eagle-import") (part "NEOPIXEL_1.5X1.5"))
    )
    (comp (ref "U25")
      (value "SK6805-E-J")
      (footprint "eagle-import:NEOPIXEL-1.5X1.5")
      (libsource (lib "eagle-import") (part "NEOPIXEL_1.5X1.5"))
    )
    (comp (ref "U26")
      (value "SK6805-E-J")
      (footprint "eagle-import:NEOPIXEL-1.5X1.5")
      (libsource (lib "eagle-import") (part "NEOPIXEL_1.5X1.5"))
    )
    (comp (ref "U27")
      (value "SK6805-E-J")
      (footprint "eagle-import:NEOPIXEL-1.5X1.5")
      (libsource (lib "eagle-import") (part "NEOPIXEL_1.5X1.5"))
    )
    (comp (ref "U28")
      (value "SK6805-E-J")
      (footprint "eagle-import:NEOPIXEL-1.5X1.5")
      (libsource (lib "eagle-import") (part "NEOPIXEL_1.5X1.5"))
    )
    (comp (ref "U29")
      (value "SK6805-E-J")
      (footprint "eagle-import:NEOPIXEL-1.5X1.5")
      (libsource (lib "eagle-import") (part "NEOPIXEL_1.5X1.5"))
    )
    (comp (ref "U30")
      (value "SK6805-E-J")
      (footprint "eagle-import:NEOPIXEL-1.5X1.5")
      (libsource (lib "eagle-import") (part "NEOPIXEL_1.5X1.5"))
    )
    (comp (ref "U31")
      (value "SK6805-E-J")
      (footprint "eagle-import:NEOPIXEL-1.5X1.5")
      (libsource (lib "eagle-import") (part "NEOPIXEL_1.5X1.5"))
    )
    (comp (ref "U32")
      (value "SK6805-E-J")
      (footprint "eagle-import:NEOPIXEL-1.5X1.5")
      (libsource (lib "eagle-import") (part "NEOPIXEL_1.5X1.5"))
    )
    (comp (ref "U33")
      (value "SK6805-E-J")
      (footprint "eagle-import:NEOPIXEL-1.5X1.5")
      (libsource (lib "eagle-import") (part "NEOPIXEL_1.5X1.5"))
    )
    (comp (ref "U34")
      (value "SK6805-E-J")
      (footprint "eagle-import:NEOPIXEL-1.5X1.5")
      (libsource (lib "eagle-import") (part "NEOPIXEL_1.5X1.5"))
    )
    (comp (ref "U35")
      (value "SK6805-E-J")
      (footprint "eagle-import:NEOPIXEL-1.5X1.5")
      (libsource (lib "eagle-import") (part "NEOPIXEL_1.5X1.5"))
    )
    (comp (ref "U36")
      (value "SK6805-E-J")
      (footprint "eagle-import:NEOPIXEL-1.5X1.5")
      (libsource (lib "eagle-import") (part "NEOPIXEL_1.5X1.5"))
    )
    (comp (ref "U37")
      (value "SK6805-E-J")
      (footprint "eagle-import:NEOPIXEL-1.5X1.5")
      (libsource (lib "eagle-import") (part "NEOPIXEL_1.5X1.5"))
    )
    (comp (ref "U38")
      (value "SK6805-E-J")
      (footprint "eagle-import:NEOPIXEL-1.5X1.5")
      (libsource (lib "eagle-import") (part "NEOPIXEL_1.5X1.5"))
    )
    (comp (ref "U39")
      (value "SK6805-E-J")
      (footprint "eagle-import:NEOPIXEL-1.5X1.5")
      (libsource (lib "eagle-import") (part "NEOPIXEL_1.5X1.5"))
    )
    (comp (ref "U40")
      (value "SK6805-E-J")
      (footprint "eagle-import:NEOPIXEL-1.5X1.5")
      (libsource (lib "eagle-import") (part "NEOPIXEL_1.5X1.5"))
    )
    (comp (ref "U41")
      (value "SK6805-E-J")
      (footprint "eagle-import:NEOPIXEL-1.5X1.5")
      (libsource (lib "eagle-import") (part "NEOPIXEL_1.5X1.5"))
    )
    (comp (ref "U42")
      (value "SK6805-E-J")
      (footprint "eagle-import:NEOPIXEL-1.5X1.5")
      (libsource (lib "eagle-import") (part "NEOPIXEL_1.5X1.5"))
    )
    (comp (ref "U43")
      (value "G6K-2F-RF")
      (footprint "eagle-import:G6KU-2F-RF")
      (libsource (lib "eagle-import") (part "G6KU-2F-RF-TR09DC5"))
    )
    (comp (ref "U44")
      (value "G6K-2F-RF")
      (footprint "eagle-import:G6KU-2F-RF")
      (libsource (lib "eagle-import") (part "G6KU-2F-RF-TR09DC5"))
    )
    (comp (ref "U45")
      (value "G6K-2F-RF")
      (footprint "eagle-import:G6KU-2F-RF")
      (libsource (lib "eagle-import") (part "G6KU-2F-RF-TR09DC5"))
    )
    (comp (ref "U46")
      (value "G6K-2F-RF")
      (footprint "eagle-import:G6KU-2F-RF")
      (libsource (lib "eagle-import") (part "G6KU-2F-RF-TR09DC5"))
    )
    (comp (ref "U47")
      (value "LTM4622A")
      (footprint "eagle-import:BGA_5X5_625X625")
      (libsource (lib "eagle-import") (part "LTM4622_BGA"))
    )
    (comp (ref "U48")
      (value "SI8610")
      (footprint "eagle-import:SO-08")
      (libsource (lib "eagle-import") (part "SI8610"))
    )
    (comp (ref "U49")
      (value "TINY-FPGA-BX")
      (footprint "eagle-import:TINY-FPGA-BX_BASIC")
      (libsource (lib "eagle-import") (part "TINY-FPGA-BX_BASIC"))
    )
    (comp (ref "U50")
      (value "TCA9555")
      (footprint "eagle-import:TSSOP-24")
      (libsource (lib "eagle-import") (part "TCA9555"))
    )
    (comp (ref "U51")
      (value "FIN1032MTCX")
      (footprint "eagle-import:TSSOP-16")
      (libsource (lib "eagle-import") (part "LVDS_RECEIVER_QUAD_TSSOP"))
    )
    (comp (ref "U52")
      (value "SN65LVDS9638DGN")
      (footprint "eagle-import:MSOP-8-PAD-3X3")
      (libsource (lib "eagle-import") (part "LVDS_DRIVER_DUAL_MSOP"))
    )
    (comp (ref "U53")
      (value "SN65LVDS9638DGN")
      (footprint "eagle-import:MSOP-8-PAD-3X3")
      (libsource (lib "eagle-import") (part "LVDS_DRIVER_DUAL_MSOP"))
    )
    (comp (ref "X")
      (value "OE-LOGO_28X20")
      (footprint "eagle-import:OE-LOGO-28X20")
      (libsource (lib "eagle-import") (part "OE-LOGO_28X20"))
    )
  )
  (nets
    (net (code "1") (name "+3V3") (class "Default")
      (node (ref "C1") (pin "1") (pinfunction "1_1") (pintype "passive"))
      (node (ref "C37") (pin "2") (pinfunction "2_2") (pintype "passive"))
      (node (ref "C43") (pin "2") (pinfunction "2_2") (pintype "passive"))
      (node (ref "C44") (pin "1") (pinfunction "1_1") (pintype "passive"))
      (node (ref "C45") (pin "1") (pinfunction "1_1") (pintype "passive"))
      (node (ref "C46") (pin "1") (pinfunction "1_1") (pintype "passive"))
      (node (ref "C47") (pin "1") (pinfunction "1_1") (pintype "passive"))
      (node (ref "C48") (pin "1") (pinfunction "1_1") (pintype "passive"))
      (node (ref "C49") (pin "1") (pinfunction "1_1") (pintype "passive"))
      (node (ref "D17") (pin "2") (pinfunction "C_2") (pintype "passive"))
      (node (ref "D18") (pin "2") (pinfunction "C_2") (pintype "passive"))
      (node (ref "D19") (pin "2") (pinfunction "C_2") (pintype "passive"))
      (node (ref "D20") (pin "2") (pinfunction "C_2") (pintype "passive"))
      (node (ref "D21") (pin "8") (pinfunction "VCC_8") (pintype "power_in"))
      (node (ref "D22") (pin "2") (pinfunction "C_2") (pintype "passive"))
      (node (ref "D23") (pin "2") (pinfunction "C_2") (pintype "passive"))
      (node (ref "D24") (pin "2") (pinfunction "C_2") (pintype "passive"))
      (node (ref "D25") (pin "2") (pinfunction "C_2") (pintype "passive"))
      (node (ref "D26") (pin "2") (pinfunction "C_2") (pintype "passive"))
      (node (ref "D27") (pin "2") (pinfunction "C_2") (pintype "passive"))
      (node (ref "D28") (pin "2") (pinfunction "C_2") (pintype "passive"))
      (node (ref "D29") (pin "2") (pinfunction "C_2") (pintype "passive"))
      (node (ref "D30") (pin "8") (pinfunction "VCC_8") (pintype "power_in"))
      (node (ref "D31") (pin "2") (pinfunction "C_2") (pintype "passive"))
      (node (ref "D32") (pin "2") (pinfunction "C_2") (pintype "passive"))
      (node (ref "D33") (pin "2") (pinfunction "C_2") (pintype "passive"))
      (node (ref "D34") (pin "2") (pinfunction "C_2") (pintype "passive"))
      (node (ref "R2") (pin "1") (pinfunction "1_1") (pintype "passive"))
      (node (ref "R22") (pin "1") (pinfunction "1_1") (pintype "passive"))
      (node (ref "R23") (pin "1") (pinfunction "1_1") (pintype "passive"))
      (node (ref "R24") (pin "1") (pinfunction "1_1") (pintype "passive"))
      (node (ref "TP1") (pin "TP") (pinfunction "TP_TP") (pintype "bidirectional"))
      (node (ref "U10") (pin "1") (pinfunction "VCCA_1") (pintype "power_in"))
      (node (ref "U47") (pin "D1") (pinfunction "VOUT1_D1") (pintype "power_in"))
      (node (ref "U47") (pin "E1") (pinfunction "VOUT1_E1") (pintype "power_in"))
      (node (ref "U50") (pin "24") (pinfunction "VCC_24") (pintype "bidirectional"))
      (node (ref "U51") (pin "16") (pinfunction "VCC_16") (pintype "power_in"))
      (node (ref "U51") (pin "4") (pinfunction "EN_4") (pintype "input"))
      (node (ref "U52") (pin "1") (pinfunction "VCC_1") (pintype "power_in"))
      (node (ref "U53") (pin "1") (pinfunction "VCC_1") (pintype "power_in"))
    )
    (net (code "2") (name "+5V") (class "Default")
      (node (ref "C10") (pin "2") (pinfunction "2_2") (pintype "passive"))
      (node (ref "C11") (pin "2") (pinfunction "2_2") (pintype "passive"))
      (node (ref "C12") (pin "2") (pinfunction "2_2") (pintype "passive"))
      (node (ref "C13") (pin "2") (pinfunction "2_2") (pintype "passive"))
      (node (ref "C14") (pin "2") (pinfunction "2_2") (pintype "passive"))
      (node (ref "C15") (pin "2") (pinfunction "2_2") (pintype "passive"))
      (node (ref "C16") (pin "2") (pinfunction "2_2") (pintype "passive"))
      (node (ref "C17") (pin "2") (pinfunction "2_2") (pintype "passive"))
      (node (ref "C18") (pin "2") (pinfunction "2_2") (pintype "passive"))
      (node (ref "C19") (pin "2") (pinfunction "2_2") (pintype "passive"))
      (node (ref "C2") (pin "1") (pinfunction "1_1") (pintype "passive"))
      (node (ref "C20") (pin "2") (pinfunction "2_2") (pintype "passive"))
      (node (ref "C21") (pin "2") (pinfunction "2_2") (pintype "passive"))
      (node (ref "C22") (pin "2") (pinfunction "2_2") (pintype "passive"))
      (node (ref "C23") (pin "2") (pinfunction "2_2") (pintype "passive"))
      (node (ref "C24") (pin "2") (pinfunction "2_2") (pintype "passive"))
      (node (ref "C25") (pin "2") (pinfunction "2_2") (pintype "passive"))
      (node (ref "C26") (pin "2") (pinfunction "2_2") (pintype "passive"))
      (node (ref "C27") (pin "2") (pinfunction "2_2") (pintype "passive"))
      (node (ref "C3") (pin "2") (pinfunction "2_2") (pintype "passive"))
      (node (ref "C36") (pin "2") (pinfunction "2_2") (pintype "passive"))
      (node (ref "C4") (pin "2") (pinfunction "2_2") (pintype "passive"))
      (node (ref "C42") (pin "2") (pinfunction "2_2") (pintype "passive"))
      (node (ref "C5") (pin "2") (pinfunction "2_2") (pintype "passive"))
      (node (ref "C6") (pin "2") (pinfunction "2_2") (pintype "passive"))
      (node (ref "C7") (pin "2") (pinfunction "2_2") (pintype "passive"))
      (node (ref "C8") (pin "2") (pinfunction "2_2") (pintype "passive"))
      (node (ref "C9") (pin "2") (pinfunction "2_2") (pintype "passive"))
      (node (ref "D1") (pin "C") (pinfunction "C_C") (pintype "passive"))
      (node (ref "D2") (pin "C") (pinfunction "C_C") (pintype "passive"))
      (node (ref "D3") (pin "C") (pinfunction "C_C") (pintype "passive"))
      (node (ref "D4") (pin "C") (pinfunction "C_C") (pintype "passive"))
      (node (ref "S1") (pin "3") (pinfunction "3_3") (pintype "passive"))
      (node (ref "S2") (pin "3") (pinfunction "3_3") (pintype "passive"))
      (node (ref "S3") (pin "3") (pinfunction "3_3") (pintype "passive"))
      (node (ref "S4") (pin "3") (pinfunction "3_3") (pintype "passive"))
      (node (ref "TP2") (pin "TP") (pinfunction "TP_TP") (pintype "bidirectional"))
      (node (ref "U1") (pin "2") (pinfunction "VDD_2") (pintype "power_in"))
      (node (ref "U10") (pin "6") (pinfunction "VCCB_6") (pintype "power_in"))
      (node (ref "U11") (pin "2") (pinfunction "VDD_2") (pintype "power_in"))
      (node (ref "U12") (pin "2") (pinfunction "VDD_2") (pintype "power_in"))
      (node (ref "U13") (pin "2") (pinfunction "VDD_2") (pintype "power_in"))
      (node (ref "U14") (pin "2") (pinfunction "VDD_2") (pintype "power_in"))
      (node (ref "U15") (pin "2") (pinfunction "VDD_2") (pintype "power_in"))
      (node (ref "U16") (pin "2") (pinfunction "VDD_2") (pintype "power_in"))
      (node (ref "U17") (pin "2") (pinfunction "VDD_2") (pintype "power_in"))
      (node (ref "U18") (pin "2") (pinfunction "VDD_2") (pintype "power_in"))
      (node (ref "U19") (pin "2") (pinfunction "VDD_2") (pintype "power_in"))
      (node (ref "U2") (pin "2") (pinfunction "VDD_2") (pintype "power_in"))
      (node (ref "U20") (pin "2") (pinfunction "VDD_2") (pintype "power_in"))
      (node (ref "U21") (pin "2") (pinfunction "VDD_2") (pintype "power_in"))
      (node (ref "U22") (pin "2") (pinfunction "VDD_2") (pintype "power_in"))
      (node (ref "U23") (pin "2") (pinfunction "VDD_2") (pintype "power_in"))
      (node (ref "U24") (pin "2") (pinfunction "VDD_2") (pintype "power_in"))
      (node (ref "U25") (pin "2") (pinfunction "VDD_2") (pintype "power_in"))
      (node (ref "U26") (pin "2") (pinfunction "VDD_2") (pintype "power_in"))
      (node (ref "U27") (pin "2") (pinfunction "VDD_2") (pintype "power_in"))
      (node (ref "U28") (pin "2") (pinfunction "VDD_2") (pintype "power_in"))
      (node (ref "U29") (pin "2") (pinfunction "VDD_2") (pintype "power_in"))
      (node (ref "U3") (pin "2") (pinfunction "VDD_2") (pintype "power_in"))
      (node (ref "U30") (pin "2") (pinfunction "VDD_2") (pintype "power_in"))
      (node (ref "U31") (pin "2") (pinfunction "VDD_2") (pintype "power_in"))
      (node (ref "U32") (pin "2") (pinfunction "VDD_2") (pintype "power_in"))
      (node (ref "U33") (pin "2") (pinfunction "VDD_2") (pintype "power_in"))
      (node (ref "U34") (pin "2") (pinfunction "VDD_2") (pintype "power_in"))
      (node (ref "U35") (pin "2") (pinfunction "VDD_2") (pintype "power_in"))
      (node (ref "U36") (pin "2") (pinfunction "VDD_2") (pintype "power_in"))
      (node (ref "U37") (pin "2") (pinfunction "VDD_2") (pintype "power_in"))
      (node (ref "U38") (pin "2") (pinfunction "VDD_2") (pintype "power_in"))
      (node (ref "U39") (pin "2") (pinfunction "VDD_2") (pintype "power_in"))
      (node (ref "U4") (pin "2") (pinfunction "VDD_2") (pintype "power_in"))
      (node (ref "U40") (pin "2") (pinfunction "VDD_2") (pintype "power_in"))
      (node (ref "U41") (pin "2") (pinfunction "VDD_2") (pintype "power_in"))
      (node (ref "U42") (pin "2") (pinfunction "VDD_2") (pintype "power_in"))
      (node (ref "U43") (pin "1") (pinfunction "COIL+_1") (pintype "bidirectional"))
      (node (ref "U44") (pin "1") (pinfunction "COIL+_1") (pintype "bidirectional"))
      (node (ref "U45") (pin "1") (pinfunction "COIL+_1") (pintype "bidirectional"))
      (node (ref "U46") (pin "1") (pinfunction "COIL+_1") (pintype "bidirectional"))
      (node (ref "U47") (pin "A1") (pinfunction "VOUT2_A1") (pintype "power_in"))
      (node (ref "U47") (pin "B1") (pinfunction "VOUT2_B1") (pintype "power_in"))
      (node (ref "U48") (pin "1") (pinfunction "AVDD_1") (pintype "bidirectional"))
      (node (ref "U49") (pin "VIN") (pinfunction "VIN_VIN") (pintype "power_in"))
      (node (ref "U5") (pin "2") (pinfunction "VDD_2") (pintype "power_in"))
      (node (ref "U6") (pin "2") (pinfunction "VDD_2") (pintype "power_in"))
      (node (ref "U7") (pin "2") (pinfunction "VDD_2") (pintype "power_in"))
      (node (ref "U8") (pin "2") (pinfunction "VDD_2") (pintype "power_in"))
      (node (ref "U9") (pin "2") (pinfunction "VDD_2") (pintype "power_in"))
    )
    (net (code "3") (name "+12V") (class "Default")
      (node (ref "C40") (pin "2") (pinfunction "2_2") (pintype "passive"))
      (node (ref "J32") (pin "1") (pinfunction "1_1") (pintype "bidirectional"))
      (node (ref "J32") (pin "26") (pinfunction "26_26") (pintype "bidirectional"))
      (node (ref "TP7") (pin "1") (pinfunction "TP_1") (pintype "bidirectional"))
      (node (ref "U47") (pin "A2") (pinfunction "VIN_A2") (pintype "power_in"))
      (node (ref "U47") (pin "B2") (pinfunction "RUN2_B2") (pintype "input"))
      (node (ref "U47") (pin "B3") (pinfunction "VIN_B3") (pintype "power_in"))
      (node (ref "U47") (pin "D2") (pinfunction "RUN1_D2") (pintype "input"))
      (node (ref "U47") (pin "D3") (pinfunction "VIN_D3") (pintype "power_in"))
      (node (ref "U47") (pin "E2") (pinfunction "VIN_E2") (pintype "power_in"))
    )
    (net (code "4") (name "/3.3V") (class "Default")
      (node (ref "U49") (pin "3.3V") (pinfunction "3.3V_3.3V") (pintype "power_in"))
    )
    (net (code "5") (name "/LVDS_DIN0_N") (class "Default")
      (node (ref "J32") (pin "23") (pinfunction "23_23") (pintype "bidirectional"))
      (node (ref "U52") (pin "5") (pinfunction "BOUT-_5") (pintype "output"))
    )
    (net (code "6") (name "/LVDS_DIN0_P") (class "Default")
      (node (ref "J32") (pin "10") (pinfunction "10_10") (pintype "bidirectional"))
      (node (ref "U52") (pin "6") (pinfunction "BOUT+_6") (pintype "output"))
    )
    (net (code "7") (name "/LVDS_DIN1_N") (class "Default")
      (node (ref "J32") (pin "11") (pinfunction "11_11") (pintype "bidirectional"))
      (node (ref "U52") (pin "7") (pinfunction "AOUT-_7") (pintype "output"))
    )
    (net (code "8") (name "/LVDS_DIN1_P") (class "Default")
      (node (ref "J32") (pin "24") (pinfunction "24_24") (pintype "bidirectional"))
      (node (ref "U52") (pin "8") (pinfunction "AOUT+_8") (pintype "output"))
    )
    (net (code "9") (name "/LVDS_DIN2_N") (class "Default")
      (node (ref "J32") (pin "25") (pinfunction "25_25") (pintype "bidirectional"))
      (node (ref "U53") (pin "7") (pinfunction "AOUT-_7") (pintype "output"))
    )
    (net (code "10") (name "/LVDS_DIN2_P") (class "Default")
      (node (ref "J32") (pin "12") (pinfunction "12_12") (pintype "bidirectional"))
      (node (ref "U53") (pin "8") (pinfunction "AOUT+_8") (pintype "output"))
    )
    (net (code "11") (name "/LVDS_DOUT0_N") (class "Default")
      (node (ref "J32") (pin "8") (pinfunction "8_8") (pintype "bidirectional"))
      (node (ref "R25") (pin "1") (pinfunction "1_1") (pintype "passive"))
      (node (ref "U51") (pin "1") (pinfunction "A-_1") (pintype "input"))
    )
    (net (code "12") (name "/LVDS_DOUT0_P") (class "Default")
      (node (ref "J32") (pin "21") (pinfunction "21_21") (pintype "bidirectional"))
      (node (ref "R25") (pin "2") (pinfunction "2_2") (pintype "passive"))
      (node (ref "U51") (pin "2") (pinfunction "A+_2") (pintype "input"))
    )
    (net (code "13") (name "/LVDS_DOUT1_N") (class "Default")
      (node (ref "J32") (pin "9") (pinfunction "9_9") (pintype "bidirectional"))
      (node (ref "R26") (pin "1") (pinfunction "1_1") (pintype "passive"))
      (node (ref "U51") (pin "7") (pinfunction "B-_7") (pintype "input"))
    )
    (net (code "14") (name "/LVDS_DOUT1_P") (class "Default")
      (node (ref "J32") (pin "22") (pinfunction "22_22") (pintype "bidirectional"))
      (node (ref "R26") (pin "2") (pinfunction "2_2") (pintype "passive"))
      (node (ref "U51") (pin "6") (pinfunction "B+_6") (pintype "input"))
    )
    (net (code "15") (name "/~{TCA_INT}") (class "Default")
      (node (ref "R22") (pin "2") (pinfunction "2_2") (pintype "passive"))
      (node (ref "U50") (pin "1") (pinfunction "_INT_1") (pintype "bidirectional"))
    )
    (net (code "16") (name "AGND") (class "Default")
      (node (ref "D10") (pin "A") (pinfunction "1_A") (pintype "passive"))
      (node (ref "D11") (pin "A") (pinfunction "1_A") (pintype "passive"))
      (node (ref "D12") (pin "A") (pinfunction "1_A") (pintype "passive"))
      (node (ref "D13") (pin "A") (pinfunction "1_A") (pintype "passive"))
      (node (ref "D14") (pin "A") (pinfunction "1_A") (pintype "passive"))
      (node (ref "D15") (pin "A") (pinfunction "1_A") (pintype "passive"))
      (node (ref "D16") (pin "A") (pinfunction "1_A") (pintype "passive"))
      (node (ref "D5") (pin "A") (pinfunction "1_A") (pintype "passive"))
      (node (ref "D6") (pin "A") (pinfunction "1_A") (pintype "passive"))
      (node (ref "D7") (pin "A") (pinfunction "1_A") (pintype "passive"))
      (node (ref "D8") (pin "A") (pinfunction "1_A") (pintype "passive"))
      (node (ref "D9") (pin "A") (pinfunction "1_A") (pintype "passive"))
      (node (ref "J10") (pin "2") (pinfunction "2_2") (pintype "passive"))
      (node (ref "J10") (pin "3") (pinfunction "2_3") (pintype "passive"))
      (node (ref "J10") (pin "4") (pinfunction "2_4") (pintype "passive"))
      (node (ref "J10") (pin "5") (pinfunction "2_5") (pintype "passive"))
      (node (ref "J11") (pin "2") (pinfunction "2_2") (pintype "passive"))
      (node (ref "J11") (pin "3") (pinfunction "2_3") (pintype "passive"))
      (node (ref "J11") (pin "4") (pinfunction "2_4") (pintype "passive"))
      (node (ref "J11") (pin "5") (pinfunction "2_5") (pintype "passive"))
      (node (ref "J12") (pin "2") (pinfunction "2_2") (pintype "passive"))
      (node (ref "J12") (pin "3") (pinfunction "2_3") (pintype "passive"))
      (node (ref "J12") (pin "4") (pinfunction "2_4") (pintype "passive"))
      (node (ref "J12") (pin "5") (pinfunction "2_5") (pintype "passive"))
      (node (ref "J13") (pin "2") (pinfunction "2_2") (pintype "passive"))
      (node (ref "J13") (pin "3") (pinfunction "2_3") (pintype "passive"))
      (node (ref "J13") (pin "4") (pinfunction "2_4") (pintype "passive"))
      (node (ref "J13") (pin "5") (pinfunction "2_5") (pintype "passive"))
      (node (ref "J14") (pin "2") (pinfunction "2_2") (pintype "passive"))
      (node (ref "J14") (pin "3") (pinfunction "2_3") (pintype "passive"))
      (node (ref "J14") (pin "4") (pinfunction "2_4") (pintype "passive"))
      (node (ref "J14") (pin "5") (pinfunction "2_5") (pintype "passive"))
      (node (ref "J17") (pin "1") (pinfunction "1_1") (pintype "passive"))
      (node (ref "J17") (pin "15") (pinfunction "15_15") (pintype "passive"))
      (node (ref "J17") (pin "16") (pinfunction "16_16") (pintype "passive"))
      (node (ref "J17") (pin "17") (pinfunction "1_17") (pintype "passive"))
      (node (ref "J17") (pin "18") (pinfunction "2_18") (pintype "passive"))
      (node (ref "J17") (pin "2") (pinfunction "2_2") (pintype "passive"))
      (node (ref "J17") (pin "31") (pinfunction "15_31") (pintype "passive"))
      (node (ref "J17") (pin "32") (pinfunction "16_32") (pintype "passive"))
      (node (ref "J20") (pin "2") (pinfunction "2_2") (pintype "passive"))
      (node (ref "J20") (pin "3") (pinfunction "2_3") (pintype "passive"))
      (node (ref "J20") (pin "4") (pinfunction "2_4") (pintype "passive"))
      (node (ref "J20") (pin "5") (pinfunction "2_5") (pintype "passive"))
      (node (ref "J21") (pin "2") (pinfunction "2_2") (pintype "passive"))
      (node (ref "J21") (pin "3") (pinfunction "2_3") (pintype "passive"))
      (node (ref "J21") (pin "4") (pinfunction "2_4") (pintype "passive"))
      (node (ref "J21") (pin "5") (pinfunction "2_5") (pintype "passive"))
      (node (ref "J22") (pin "2") (pinfunction "2_2") (pintype "passive"))
      (node (ref "J22") (pin "3") (pinfunction "2_3") (pintype "passive"))
      (node (ref "J22") (pin "4") (pinfunction "2_4") (pintype "passive"))
      (node (ref "J22") (pin "5") (pinfunction "2_5") (pintype "passive"))
      (node (ref "J23") (pin "2") (pinfunction "2_2") (pintype "passive"))
      (node (ref "J23") (pin "3") (pinfunction "2_3") (pintype "passive"))
      (node (ref "J23") (pin "4") (pinfunction "2_4") (pintype "passive"))
      (node (ref "J23") (pin "5") (pinfunction "2_5") (pintype "passive"))
      (node (ref "J24") (pin "2") (pinfunction "2_2") (pintype "passive"))
      (node (ref "J24") (pin "3") (pinfunction "2_3") (pintype "passive"))
      (node (ref "J24") (pin "4") (pinfunction "2_4") (pintype "passive"))
      (node (ref "J24") (pin "5") (pinfunction "2_5") (pintype "passive"))
      (node (ref "J25") (pin "2") (pinfunction "2_2") (pintype "passive"))
      (node (ref "J25") (pin "3") (pinfunction "2_3") (pintype "passive"))
      (node (ref "J25") (pin "4") (pinfunction "2_4") (pintype "passive"))
      (node (ref "J25") (pin "5") (pinfunction "2_5") (pintype "passive"))
      (node (ref "J26") (pin "1") (pinfunction "1_1") (pintype "bidirectional"))
      (node (ref "J26") (pin "11") (pinfunction "11_11") (pintype "bidirectional"))
      (node (ref "J26") (pin "13") (pinfunction "13_13") (pintype "bidirectional"))
      (node (ref "J26") (pin "15") (pinfunction "15_15") (pintype "bidirectional"))
      (node (ref "J26") (pin "17") (pinfunction "17_17") (pintype "bidirectional"))
      (node (ref "J26") (pin "19") (pinfunction "19_19") (pintype "bidirectional"))
      (node (ref "J26") (pin "21") (pinfunction "21_21") (pintype "bidirectional"))
      (node (ref "J26") (pin "23") (pinfunction "23_23") (pintype "bidirectional"))
      (node (ref "J26") (pin "3") (pinfunction "3_3") (pintype "bidirectional"))
      (node (ref "J26") (pin "5") (pinfunction "5_5") (pintype "bidirectional"))
      (node (ref "J26") (pin "7") (pinfunction "7_7") (pintype "bidirectional"))
      (node (ref "J26") (pin "9") (pinfunction "9_9") (pintype "bidirectional"))
      (node (ref "J32") (pin "13") (pinfunction "13_13") (pintype "bidirectional"))
      (node (ref "J32") (pin "14") (pinfunction "14_14") (pintype "bidirectional"))
      (node (ref "J9") (pin "2") (pinfunction "2_2") (pintype "passive"))
      (node (ref "J9") (pin "3") (pinfunction "2_3") (pintype "passive"))
      (node (ref "J9") (pin "4") (pinfunction "2_4") (pintype "passive"))
      (node (ref "J9") (pin "5") (pinfunction "2_5") (pintype "passive"))
      (node (ref "TP6") (pin "1") (pinfunction "TP_1") (pintype "bidirectional"))
    )
    (net (code "17") (name "AIO_0") (class "Default")
      (node (ref "D5") (pin "C") (pinfunction "2_C") (pintype "passive"))
      (node (ref "J17") (pin "19") (pinfunction "3_19") (pintype "passive"))
      (node (ref "J17") (pin "3") (pinfunction "3_3") (pintype "passive"))
      (node (ref "J26") (pin "2") (pinfunction "2_2") (pintype "bidirectional"))
      (node (ref "J32") (pin "20") (pinfunction "20_20") (pintype "bidirectional"))
      (node (ref "J9") (pin "1") (pinfunction "1_1") (pintype "passive"))
    )
    (net (code "18") (name "AIO_1") (class "Default")
      (node (ref "D6") (pin "C") (pinfunction "2_C") (pintype "passive"))
      (node (ref "J10") (pin "1") (pinfunction "1_1") (pintype "passive"))
      (node (ref "J17") (pin "20") (pinfunction "4_20") (pintype "passive"))
      (node (ref "J17") (pin "4") (pinfunction "4_4") (pintype "passive"))
      (node (ref "J26") (pin "4") (pinfunction "4_4") (pintype "bidirectional"))
      (node (ref "J32") (pin "7") (pinfunction "7_7") (pintype "bidirectional"))
    )
    (net (code "19") (name "AIO_2") (class "Default")
      (node (ref "D7") (pin "C") (pinfunction "2_C") (pintype "passive"))
      (node (ref "J11") (pin "1") (pinfunction "1_1") (pintype "passive"))
      (node (ref "J17") (pin "21") (pinfunction "5_21") (pintype "passive"))
      (node (ref "J17") (pin "5") (pinfunction "5_5") (pintype "passive"))
      (node (ref "J26") (pin "6") (pinfunction "6_6") (pintype "bidirectional"))
      (node (ref "J32") (pin "19") (pinfunction "19_19") (pintype "bidirectional"))
    )
    (net (code "20") (name "AIO_3") (class "Default")
      (node (ref "D8") (pin "C") (pinfunction "2_C") (pintype "passive"))
      (node (ref "J12") (pin "1") (pinfunction "1_1") (pintype "passive"))
      (node (ref "J17") (pin "22") (pinfunction "6_22") (pintype "passive"))
      (node (ref "J17") (pin "6") (pinfunction "6_6") (pintype "passive"))
      (node (ref "J26") (pin "8") (pinfunction "8_8") (pintype "bidirectional"))
      (node (ref "J32") (pin "6") (pinfunction "6_6") (pintype "bidirectional"))
    )
    (net (code "21") (name "AIO_4") (class "Default")
      (node (ref "D9") (pin "C") (pinfunction "2_C") (pintype "passive"))
      (node (ref "J13") (pin "1") (pinfunction "1_1") (pintype "passive"))
      (node (ref "J17") (pin "23") (pinfunction "7_23") (pintype "passive"))
      (node (ref "J17") (pin "7") (pinfunction "7_7") (pintype "passive"))
      (node (ref "J26") (pin "10") (pinfunction "10_10") (pintype "bidirectional"))
      (node (ref "J32") (pin "18") (pinfunction "18_18") (pintype "bidirectional"))
    )
    (net (code "22") (name "AIO_5") (class "Default")
      (node (ref "D10") (pin "C") (pinfunction "2_C") (pintype "passive"))
      (node (ref "J14") (pin "1") (pinfunction "1_1") (pintype "passive"))
      (node (ref "J17") (pin "24") (pinfunction "8_24") (pintype "passive"))
      (node (ref "J17") (pin "8") (pinfunction "8_8") (pintype "passive"))
      (node (ref "J26") (pin "12") (pinfunction "12_12") (pintype "bidirectional"))
      (node (ref "J32") (pin "5") (pinfunction "5_5") (pintype "bidirectional"))
    )
    (net (code "23") (name "AIO_6") (class "Default")
      (node (ref "D11") (pin "C") (pinfunction "2_C") (pintype "passive"))
      (node (ref "J17") (pin "25") (pinfunction "9_25") (pintype "passive"))
      (node (ref "J17") (pin "9") (pinfunction "9_9") (pintype "passive"))
      (node (ref "J20") (pin "1") (pinfunction "1_1") (pintype "passive"))
      (node (ref "J26") (pin "14") (pinfunction "14_14") (pintype "bidirectional"))
      (node (ref "J32") (pin "17") (pinfunction "17_17") (pintype "bidirectional"))
    )
    (net (code "24") (name "AIO_7") (class "Default")
      (node (ref "D12") (pin "C") (pinfunction "2_C") (pintype "passive"))
      (node (ref "J17") (pin "10") (pinfunction "10_10") (pintype "passive"))
      (node (ref "J17") (pin "26") (pinfunction "10_26") (pintype "passive"))
      (node (ref "J21") (pin "1") (pinfunction "1_1") (pintype "passive"))
      (node (ref "J26") (pin "16") (pinfunction "16_16") (pintype "bidirectional"))
      (node (ref "J32") (pin "4") (pinfunction "4_4") (pintype "bidirectional"))
    )
    (net (code "25") (name "AIO_8") (class "Default")
      (node (ref "D13") (pin "C") (pinfunction "2_C") (pintype "passive"))
      (node (ref "J17") (pin "11") (pinfunction "11_11") (pintype "passive"))
      (node (ref "J17") (pin "27") (pinfunction "11_27") (pintype "passive"))
      (node (ref "J22") (pin "1") (pinfunction "1_1") (pintype "passive"))
      (node (ref "J26") (pin "18") (pinfunction "18_18") (pintype "bidirectional"))
      (node (ref "J32") (pin "16") (pinfunction "16_16") (pintype "bidirectional"))
    )
    (net (code "26") (name "AIO_9") (class "Default")
      (node (ref "D14") (pin "C") (pinfunction "2_C") (pintype "passive"))
      (node (ref "J17") (pin "12") (pinfunction "12_12") (pintype "passive"))
      (node (ref "J17") (pin "28") (pinfunction "12_28") (pintype "passive"))
      (node (ref "J23") (pin "1") (pinfunction "1_1") (pintype "passive"))
      (node (ref "J26") (pin "20") (pinfunction "20_20") (pintype "bidirectional"))
      (node (ref "J32") (pin "3") (pinfunction "3_3") (pintype "bidirectional"))
    )
    (net (code "27") (name "AIO_10") (class "Default")
      (node (ref "D15") (pin "C") (pinfunction "2_C") (pintype "passive"))
      (node (ref "J17") (pin "13") (pinfunction "13_13") (pintype "passive"))
      (node (ref "J17") (pin "29") (pinfunction "13_29") (pintype "passive"))
      (node (ref "J24") (pin "1") (pinfunction "1_1") (pintype "passive"))
      (node (ref "J26") (pin "22") (pinfunction "22_22") (pintype "bidirectional"))
      (node (ref "J32") (pin "15") (pinfunction "15_15") (pintype "bidirectional"))
    )
    (net (code "28") (name "AIO_11") (class "Default")
      (node (ref "D16") (pin "C") (pinfunction "2_C") (pintype "passive"))
      (node (ref "J17") (pin "14") (pinfunction "14_14") (pintype "passive"))
      (node (ref "J17") (pin "30") (pinfunction "14_30") (pintype "passive"))
      (node (ref "J25") (pin "1") (pinfunction "1_1") (pintype "passive"))
      (node (ref "J26") (pin "24") (pinfunction "24_24") (pintype "bidirectional"))
      (node (ref "J32") (pin "2") (pinfunction "2_2") (pintype "bidirectional"))
    )
    (net (code "29") (name "BUTTON0") (class "Default")
      (node (ref "S5") (pin "SW1") (pinfunction "P_SW1") (pintype "passive"))
      (node (ref "U50") (pin "16") (pinfunction "P13_16") (pintype "bidirectional"))
    )
    (net (code "30") (name "BUTTON1") (class "Default")
      (node (ref "S7") (pin "SW1") (pinfunction "P_SW1") (pintype "passive"))
      (node (ref "U50") (pin "17") (pinfunction "P14_17") (pintype "bidirectional"))
    )
    (net (code "31") (name "BUTTON2") (class "Default")
      (node (ref "S9") (pin "SW1") (pinfunction "P_SW1") (pintype "passive"))
      (node (ref "U50") (pin "18") (pinfunction "P15_18") (pintype "bidirectional"))
    )
    (net (code "32") (name "BUTTON3") (class "Default")
      (node (ref "S6") (pin "SW1") (pinfunction "P_SW1") (pintype "passive"))
      (node (ref "U50") (pin "11") (pinfunction "P07_11") (pintype "bidirectional"))
    )
    (net (code "33") (name "BUTTON4") (class "Default")
      (node (ref "S8") (pin "SW1") (pinfunction "P_SW1") (pintype "passive"))
      (node (ref "U50") (pin "14") (pinfunction "P11_14") (pintype "bidirectional"))
    )
    (net (code "34") (name "BUTTON5") (class "Default")
      (node (ref "S10") (pin "SW1") (pinfunction "P_SW1") (pintype "passive"))
      (node (ref "U50") (pin "10") (pinfunction "P06_10") (pintype "bidirectional"))
    )
    (net (code "35") (name "DIN0") (class "Default")
      (node (ref "D30") (pin "4") (pinfunction "CH4_4") (pintype "passive"))
      (node (ref "J34") (pin "2") (pinfunction "2_2") (pintype "passive"))
      (node (ref "J35") (pin "11") (pinfunction "2_11") (pintype "passive"))
      (node (ref "J35") (pin "2") (pinfunction "2_2") (pintype "passive"))
      (node (ref "R42") (pin "2") (pinfunction "2_2") (pintype "passive"))
    )
    (net (code "36") (name "DIN0_P") (class "Default")
      (node (ref "D34") (pin "3") (pinfunction "COMM_3") (pintype "passive"))
      (node (ref "R42") (pin "1") (pinfunction "1_1") (pintype "passive"))
      (node (ref "U49") (pin "14") (pinfunction "14_14") (pintype "bidirectional"))
    )
    (net (code "37") (name "DIN1") (class "Default")
      (node (ref "D30") (pin "3") (pinfunction "CH3_3") (pintype "passive"))
      (node (ref "J34") (pin "4") (pinfunction "4_4") (pintype "passive"))
      (node (ref "J35") (pin "12") (pinfunction "3_12") (pintype "passive"))
      (node (ref "J35") (pin "3") (pinfunction "3_3") (pintype "passive"))
      (node (ref "R34") (pin "2") (pinfunction "2_2") (pintype "passive"))
    )
    (net (code "38") (name "DIN1_P") (class "Default")
      (node (ref "D25") (pin "3") (pinfunction "COMM_3") (pintype "passive"))
      (node (ref "R34") (pin "1") (pinfunction "1_1") (pintype "passive"))
      (node (ref "U49") (pin "15") (pinfunction "15_15") (pintype "bidirectional"))
    )
    (net (code "39") (name "DIN2") (class "Default")
      (node (ref "D30") (pin "2") (pinfunction "CH2_2") (pintype "passive"))
      (node (ref "J34") (pin "6") (pinfunction "6_6") (pintype "passive"))
      (node (ref "J35") (pin "13") (pinfunction "4_13") (pintype "passive"))
      (node (ref "J35") (pin "4") (pinfunction "4_4") (pintype "passive"))
      (node (ref "R40") (pin "2") (pinfunction "2_2") (pintype "passive"))
    )
    (net (code "40") (name "DIN2_P") (class "Default")
      (node (ref "D32") (pin "3") (pinfunction "COMM_3") (pintype "passive"))
      (node (ref "R40") (pin "1") (pinfunction "1_1") (pintype "passive"))
      (node (ref "U49") (pin "16") (pinfunction "16/GBIN2_16") (pintype "bidirectional"))
    )
    (net (code "41") (name "DIN3") (class "Default")
      (node (ref "D30") (pin "1") (pinfunction "CH1_1") (pintype "passive"))
      (node (ref "J34") (pin "8") (pinfunction "8_8") (pintype "passive"))
      (node (ref "J35") (pin "14") (pinfunction "5_14") (pintype "passive"))
      (node (ref "J35") (pin "5") (pinfunction "5_5") (pintype "passive"))
      (node (ref "R32") (pin "2") (pinfunction "2_2") (pintype "passive"))
    )
    (net (code "42") (name "DIN3_P") (class "Default")
      (node (ref "D23") (pin "3") (pinfunction "COMM_3") (pintype "passive"))
      (node (ref "R32") (pin "1") (pinfunction "1_1") (pintype "passive"))
      (node (ref "U49") (pin "9") (pinfunction "9/10B_9") (pintype "bidirectional"))
    )
    (net (code "43") (name "DIN4") (class "Default")
      (node (ref "D30") (pin "10") (pinfunction "CH8_10") (pintype "passive"))
      (node (ref "J34") (pin "10") (pinfunction "10_10") (pintype "passive"))
      (node (ref "J35") (pin "15") (pinfunction "6_15") (pintype "passive"))
      (node (ref "J35") (pin "6") (pinfunction "6_6") (pintype "passive"))
      (node (ref "R38") (pin "2") (pinfunction "2_2") (pintype "passive"))
    )
    (net (code "44") (name "DIN4_P") (class "Default")
      (node (ref "D29") (pin "3") (pinfunction "COMM_3") (pintype "passive"))
      (node (ref "R38") (pin "1") (pinfunction "1_1") (pintype "passive"))
      (node (ref "U49") (pin "10") (pinfunction "10/26A_10") (pintype "bidirectional"))
    )
    (net (code "45") (name "DIN5") (class "Default")
      (node (ref "D30") (pin "9") (pinfunction "CH7_9") (pintype "passive"))
      (node (ref "J34") (pin "12") (pinfunction "12_12") (pintype "passive"))
      (node (ref "J35") (pin "16") (pinfunction "7_16") (pintype "passive"))
      (node (ref "J35") (pin "7") (pinfunction "7_7") (pintype "passive"))
      (node (ref "R30") (pin "2") (pinfunction "2_2") (pintype "passive"))
    )
    (net (code "46") (name "DIN5_P") (class "Default")
      (node (ref "D20") (pin "3") (pinfunction "COMM_3") (pintype "passive"))
      (node (ref "R30") (pin "1") (pinfunction "1_1") (pintype "passive"))
      (node (ref "U49") (pin "11") (pinfunction "11_11") (pintype "bidirectional"))
    )
    (net (code "47") (name "DIN6") (class "Default")
      (node (ref "D30") (pin "7") (pinfunction "CH6_7") (pintype "passive"))
      (node (ref "J34") (pin "14") (pinfunction "14_14") (pintype "passive"))
      (node (ref "J35") (pin "17") (pinfunction "8_17") (pintype "passive"))
      (node (ref "J35") (pin "8") (pinfunction "8_8") (pintype "passive"))
      (node (ref "R36") (pin "2") (pinfunction "2_2") (pintype "passive"))
    )
    (net (code "48") (name "DIN6_P") (class "Default")
      (node (ref "D27") (pin "3") (pinfunction "COMM_3") (pintype "passive"))
      (node (ref "R36") (pin "1") (pinfunction "1_1") (pintype "passive"))
      (node (ref "U49") (pin "12") (pinfunction "12_12") (pintype "bidirectional"))
    )
    (net (code "49") (name "DIN7") (class "Default")
      (node (ref "D30") (pin "6") (pinfunction "CH5_6") (pintype "passive"))
      (node (ref "J34") (pin "16") (pinfunction "16_16") (pintype "passive"))
      (node (ref "J35") (pin "18") (pinfunction "9_18") (pintype "passive"))
      (node (ref "J35") (pin "9") (pinfunction "9_9") (pintype "passive"))
      (node (ref "R28") (pin "2") (pinfunction "2_2") (pintype "passive"))
    )
    (net (code "50") (name "DIN7_P") (class "Default")
      (node (ref "D18") (pin "3") (pinfunction "COMM_3") (pintype "passive"))
      (node (ref "R28") (pin "1") (pinfunction "1_1") (pintype "passive"))
      (node (ref "U49") (pin "13") (pinfunction "13/26B_13") (pintype "bidirectional"))
    )
    (net (code "51") (name "DOUT0") (class "Default")
      (node (ref "D21") (pin "10") (pinfunction "CH8_10") (pintype "passive"))
      (node (ref "J31") (pin "2") (pinfunction "2_2") (pintype "passive"))
      (node (ref "J33") (pin "11") (pinfunction "2_11") (pintype "passive"))
      (node (ref "J33") (pin "2") (pinfunction "2_2") (pintype "passive"))
      (node (ref "R27") (pin "2") (pinfunction "2_2") (pintype "passive"))
    )
    (net (code "52") (name "DOUT0_P") (class "Default")
      (node (ref "D17") (pin "3") (pinfunction "COMM_3") (pintype "passive"))
      (node (ref "R27") (pin "1") (pinfunction "1_1") (pintype "passive"))
      (node (ref "U49") (pin "8") (pinfunction "8_8") (pintype "bidirectional"))
    )
    (net (code "53") (name "DOUT1") (class "Default")
      (node (ref "D21") (pin "9") (pinfunction "CH7_9") (pintype "passive"))
      (node (ref "J31") (pin "4") (pinfunction "4_4") (pintype "passive"))
      (node (ref "J33") (pin "12") (pinfunction "3_12") (pintype "passive"))
      (node (ref "J33") (pin "3") (pinfunction "3_3") (pintype "passive"))
      (node (ref "R29") (pin "2") (pinfunction "2_2") (pintype "passive"))
    )
    (net (code "54") (name "DOUT1_P") (class "Default")
      (node (ref "D19") (pin "3") (pinfunction "COMM_3") (pintype "passive"))
      (node (ref "R29") (pin "1") (pinfunction "1_1") (pintype "passive"))
      (node (ref "U49") (pin "7") (pinfunction "7/10A_7") (pintype "bidirectional"))
    )
    (net (code "55") (name "DOUT2") (class "Default")
      (node (ref "D21") (pin "7") (pinfunction "CH6_7") (pintype "passive"))
      (node (ref "J31") (pin "6") (pinfunction "6_6") (pintype "passive"))
      (node (ref "J33") (pin "13") (pinfunction "4_13") (pintype "passive"))
      (node (ref "J33") (pin "4") (pinfunction "4_4") (pintype "passive"))
      (node (ref "R31") (pin "2") (pinfunction "2_2") (pintype "passive"))
    )
    (net (code "56") (name "DOUT2_P") (class "Default")
      (node (ref "D22") (pin "3") (pinfunction "COMM_3") (pintype "passive"))
      (node (ref "R31") (pin "1") (pinfunction "1_1") (pintype "passive"))
      (node (ref "U49") (pin "6") (pinfunction "6_6") (pintype "bidirectional"))
    )
    (net (code "57") (name "DOUT3") (class "Default")
      (node (ref "D21") (pin "6") (pinfunction "CH5_6") (pintype "passive"))
      (node (ref "J31") (pin "8") (pinfunction "8_8") (pintype "passive"))
      (node (ref "J33") (pin "14") (pinfunction "5_14") (pintype "passive"))
      (node (ref "J33") (pin "5") (pinfunction "5_5") (pintype "passive"))
      (node (ref "R33") (pin "2") (pinfunction "2_2") (pintype "passive"))
    )
    (net (code "58") (name "DOUT3_P") (class "Default")
      (node (ref "D24") (pin "3") (pinfunction "COMM_3") (pintype "passive"))
      (node (ref "R33") (pin "1") (pinfunction "1_1") (pintype "passive"))
      (node (ref "U49") (pin "5") (pinfunction "5/3B_5") (pintype "bidirectional"))
    )
    (net (code "59") (name "DOUT4") (class "Default")
      (node (ref "D21") (pin "1") (pinfunction "CH1_1") (pintype "passive"))
      (node (ref "J31") (pin "10") (pinfunction "10_10") (pintype "passive"))
      (node (ref "J33") (pin "15") (pinfunction "6_15") (pintype "passive"))
      (node (ref "J33") (pin "6") (pinfunction "6_6") (pintype "passive"))
      (node (ref "R35") (pin "2") (pinfunction "2_2") (pintype "passive"))
    )
    (net (code "60") (name "DOUT4_P") (class "Default")
      (node (ref "D26") (pin "3") (pinfunction "COMM_3") (pintype "passive"))
      (node (ref "R35") (pin "1") (pinfunction "1_1") (pintype "passive"))
      (node (ref "U49") (pin "4") (pinfunction "4_4") (pintype "bidirectional"))
    )
    (net (code "61") (name "DOUT5") (class "Default")
      (node (ref "D21") (pin "2") (pinfunction "CH2_2") (pintype "passive"))
      (node (ref "J31") (pin "12") (pinfunction "12_12") (pintype "passive"))
      (node (ref "J33") (pin "16") (pinfunction "7_16") (pintype "passive"))
      (node (ref "J33") (pin "7") (pinfunction "7_7") (pintype "passive"))
      (node (ref "R37") (pin "2") (pinfunction "2_2") (pintype "passive"))
    )
    (net (code "62") (name "DOUT5_P") (class "Default")
      (node (ref "D28") (pin "3") (pinfunction "COMM_3") (pintype "passive"))
      (node (ref "R37") (pin "1") (pinfunction "1_1") (pintype "passive"))
      (node (ref "U49") (pin "3") (pinfunction "3/3A_3") (pintype "bidirectional"))
    )
    (net (code "63") (name "DOUT6") (class "Default")
      (node (ref "D21") (pin "3") (pinfunction "CH3_3") (pintype "passive"))
      (node (ref "J31") (pin "14") (pinfunction "14_14") (pintype "passive"))
      (node (ref "J33") (pin "17") (pinfunction "8_17") (pintype "passive"))
      (node (ref "J33") (pin "8") (pinfunction "8_8") (pintype "passive"))
      (node (ref "R39") (pin "2") (pinfunction "2_2") (pintype "passive"))
    )
    (net (code "64") (name "DOUT6_P") (class "Default")
      (node (ref "D31") (pin "3") (pinfunction "COMM_3") (pintype "passive"))
      (node (ref "R39") (pin "1") (pinfunction "1_1") (pintype "passive"))
      (node (ref "U49") (pin "2") (pinfunction "2_2") (pintype "bidirectional"))
    )
    (net (code "65") (name "DOUT7") (class "Default")
      (node (ref "D21") (pin "4") (pinfunction "CH4_4") (pintype "passive"))
      (node (ref "J31") (pin "16") (pinfunction "16_16") (pintype "passive"))
      (node (ref "J33") (pin "18") (pinfunction "9_18") (pintype "passive"))
      (node (ref "J33") (pin "9") (pinfunction "9_9") (pintype "passive"))
      (node (ref "R41") (pin "2") (pinfunction "2_2") (pintype "passive"))
    )
    (net (code "66") (name "DOUT7_P") (class "Default")
      (node (ref "D33") (pin "3") (pinfunction "COMM_3") (pintype "passive"))
      (node (ref "R41") (pin "1") (pinfunction "1_1") (pintype "passive"))
      (node (ref "U49") (pin "1") (pinfunction "1_1") (pintype "bidirectional"))
    )
    (net (code "67") (name "GND") (class "Default")
      (node (ref "C1") (pin "2") (pinfunction "2_2") (pintype "passive"))
      (node (ref "C10") (pin "1") (pinfunction "1_1") (pintype "passive"))
      (node (ref "C11") (pin "1") (pinfunction "1_1") (pintype "passive"))
      (node (ref "C12") (pin "1") (pinfunction "1_1") (pintype "passive"))
      (node (ref "C13") (pin "1") (pinfunction "1_1") (pintype "passive"))
      (node (ref "C14") (pin "1") (pinfunction "1_1") (pintype "passive"))
      (node (ref "C15") (pin "1") (pinfunction "1_1") (pintype "passive"))
      (node (ref "C16") (pin "1") (pinfunction "1_1") (pintype "passive"))
      (node (ref "C17") (pin "1") (pinfunction "1_1") (pintype "passive"))
      (node (ref "C18") (pin "1") (pinfunction "1_1") (pintype "passive"))
      (node (ref "C19") (pin "1") (pinfunction "1_1") (pintype "passive"))
      (node (ref "C2") (pin "2") (pinfunction "2_2") (pintype "passive"))
      (node (ref "C20") (pin "1") (pinfunction "1_1") (pintype "passive"))
      (node (ref "C21") (pin "1") (pinfunction "1_1") (pintype "passive"))
      (node (ref "C22") (pin "1") (pinfunction "1_1") (pintype "passive"))
      (node (ref "C23") (pin "1") (pinfunction "1_1") (pintype "passive"))
      (node (ref "C24") (pin "1") (pinfunction "1_1") (pintype "passive"))
      (node (ref "C25") (pin "1") (pinfunction "1_1") (pintype "passive"))
      (node (ref "C26") (pin "1") (pinfunction "1_1") (pintype "passive"))
      (node (ref "C27") (pin "1") (pinfunction "1_1") (pintype "passive"))
      (node (ref "C28") (pin "1") (pinfunction "1_1") (pintype "passive"))
      (node (ref "C29") (pin "1") (pinfunction "1_1") (pintype "passive"))
      (node (ref "C3") (pin "1") (pinfunction "1_1") (pintype "passive"))
      (node (ref "C30") (pin "1") (pinfunction "1_1") (pintype "passive"))
      (node (ref "C31") (pin "1") (pinfunction "1_1") (pintype "passive"))
      (node (ref "C36") (pin "1") (pinfunction "1_1") (pintype "passive"))
      (node (ref "C37") (pin "1") (pinfunction "1_1") (pintype "passive"))
      (node (ref "C38") (pin "1") (pinfunction "1_1") (pintype "passive"))
      (node (ref "C39") (pin "1") (pinfunction "1_1") (pintype "passive"))
      (node (ref "C4") (pin "1") (pinfunction "1_1") (pintype "passive"))
      (node (ref "C40") (pin "1") (pinfunction "1_1") (pintype "passive"))
      (node (ref "C42") (pin "1") (pinfunction "1_1") (pintype "passive"))
      (node (ref "C43") (pin "1") (pinfunction "1_1") (pintype "passive"))
      (node (ref "C44") (pin "2") (pinfunction "2_2") (pintype "passive"))
      (node (ref "C45") (pin "2") (pinfunction "2_2") (pintype "passive"))
      (node (ref "C46") (pin "2") (pinfunction "2_2") (pintype "passive"))
      (node (ref "C47") (pin "2") (pinfunction "2_2") (pintype "passive"))
      (node (ref "C48") (pin "2") (pinfunction "2_2") (pintype "passive"))
      (node (ref "C49") (pin "2") (pinfunction "2_2") (pintype "passive"))
      (node (ref "C5") (pin "1") (pinfunction "1_1") (pintype "passive"))
      (node (ref "C6") (pin "1") (pinfunction "1_1") (pintype "passive"))
      (node (ref "C7") (pin "1") (pinfunction "1_1") (pintype "passive"))
      (node (ref "C8") (pin "1") (pinfunction "1_1") (pintype "passive"))
      (node (ref "C9") (pin "1") (pinfunction "1_1") (pintype "passive"))
      (node (ref "D17") (pin "1") (pinfunction "A_1") (pintype "passive"))
      (node (ref "D18") (pin "1") (pinfunction "A_1") (pintype "passive"))
      (node (ref "D19") (pin "1") (pinfunction "A_1") (pintype "passive"))
      (node (ref "D20") (pin "1") (pinfunction "A_1") (pintype "passive"))
      (node (ref "D21") (pin "5") (pinfunction "VSS_5") (pintype "power_in"))
      (node (ref "D22") (pin "1") (pinfunction "A_1") (pintype "passive"))
      (node (ref "D23") (pin "1") (pinfunction "A_1") (pintype "passive"))
      (node (ref "D24") (pin "1") (pinfunction "A_1") (pintype "passive"))
      (node (ref "D25") (pin "1") (pinfunction "A_1") (pintype "passive"))
      (node (ref "D26") (pin "1") (pinfunction "A_1") (pintype "passive"))
      (node (ref "D27") (pin "1") (pinfunction "A_1") (pintype "passive"))
      (node (ref "D28") (pin "1") (pinfunction "A_1") (pintype "passive"))
      (node (ref "D29") (pin "1") (pinfunction "A_1") (pintype "passive"))
      (node (ref "D30") (pin "5") (pinfunction "VSS_5") (pintype "power_in"))
      (node (ref "D31") (pin "1") (pinfunction "A_1") (pintype "passive"))
      (node (ref "D32") (pin "1") (pinfunction "A_1") (pintype "passive"))
      (node (ref "D33") (pin "1") (pinfunction "A_1") (pintype "passive"))
      (node (ref "D34") (pin "1") (pinfunction "A_1") (pintype "passive"))
      (node (ref "J1") (pin "GND$1") (pinfunction "2_GND$1") (pintype "passive"))
      (node (ref "J1") (pin "GND$2") (pinfunction "2_GND$2") (pintype "passive"))
      (node (ref "J1") (pin "GND$3") (pinfunction "2_GND$3") (pintype "passive"))
      (node (ref "J1") (pin "GND$4") (pinfunction "2_GND$4") (pintype "passive"))
      (node (ref "J15") (pin "GND@1") (pinfunction "2_GND@1") (pintype "passive"))
      (node (ref "J15") (pin "GND@2") (pinfunction "2_GND@2") (pintype "passive"))
      (node (ref "J15") (pin "GND@3") (pinfunction "2_GND@3") (pintype "passive"))
      (node (ref "J15") (pin "GND@4") (pinfunction "2_GND@4") (pintype "passive"))
      (node (ref "J16") (pin "GND$1") (pinfunction "2_GND$1") (pintype "passive"))
      (node (ref "J16") (pin "GND$2") (pinfunction "2_GND$2") (pintype "passive"))
      (node (ref "J16") (pin "GND$3") (pinfunction "2_GND$3") (pintype "passive"))
      (node (ref "J16") (pin "GND$4") (pinfunction "2_GND$4") (pintype "passive"))
      (node (ref "J18") (pin "GND@1") (pinfunction "2_GND@1") (pintype "passive"))
      (node (ref "J18") (pin "GND@2") (pinfunction "2_GND@2") (pintype "passive"))
      (node (ref "J18") (pin "GND@3") (pinfunction "2_GND@3") (pintype "passive"))
      (node (ref "J18") (pin "GND@4") (pinfunction "2_GND@4") (pintype "passive"))
      (node (ref "J19") (pin "GND$1") (pinfunction "2_GND$1") (pintype "passive"))
      (node (ref "J19") (pin "GND$2") (pinfunction "2_GND$2") (pintype "passive"))
      (node (ref "J19") (pin "GND$3") (pinfunction "2_GND$3") (pintype "passive"))
      (node (ref "J19") (pin "GND$4") (pinfunction "2_GND$4") (pintype "passive"))
      (node (ref "J2") (pin "GND$1") (pinfunction "2_GND$1") (pintype "passive"))
      (node (ref "J2") (pin "GND$2") (pinfunction "2_GND$2") (pintype "passive"))
      (node (ref "J2") (pin "GND$3") (pinfunction "2_GND$3") (pintype "passive"))
      (node (ref "J2") (pin "GND$4") (pinfunction "2_GND$4") (pintype "passive"))
      (node (ref "J27") (pin "GND@1") (pinfunction "2_GND@1") (pintype "passive"))
      (node (ref "J27") (pin "GND@2") (pinfunction "2_GND@2") (pintype "passive"))
      (node (ref "J27") (pin "GND@3") (pinfunction "2_GND@3") (pintype "passive"))
      (node (ref "J27") (pin "GND@4") (pinfunction "2_GND@4") (pintype "passive"))
      (node (ref "J28") (pin "GND$1") (pinfunction "2_GND$1") (pintype "passive"))
      (node (ref "J28") (pin "GND$2") (pinfunction "2_GND$2") (pintype "passive"))
      (node (ref "J28") (pin "GND$3") (pinfunction "2_GND$3") (pintype "passive"))
      (node (ref "J28") (pin "GND$4") (pinfunction "2_GND$4") (pintype "passive"))
      (node (ref "J3") (pin "GND$1") (pinfunction "2_GND$1") (pintype "passive"))
      (node (ref "J3") (pin "GND$2") (pinfunction "2_GND$2") (pintype "passive"))
      (node (ref "J3") (pin "GND$3") (pinfunction "2_GND$3") (pintype "passive"))
      (node (ref "J3") (pin "GND$4") (pinfunction "2_GND$4") (pintype "passive"))
      (node (ref "J30") (pin "2") (pinfunction "2_2") (pintype "passive"))
      (node (ref "J31") (pin "1") (pinfunction "1_1") (pintype "passive"))
      (node (ref "J31") (pin "11") (pinfunction "11_11") (pintype "passive"))
      (node (ref "J31") (pin "13") (pinfunction "13_13") (pintype "passive"))
      (node (ref "J31") (pin "15") (pinfunction "15_15") (pintype "passive"))
      (node (ref "J31") (pin "3") (pinfunction "3_3") (pintype "passive"))
      (node (ref "J31") (pin "5") (pinfunction "5_5") (pintype "passive"))
      (node (ref "J31") (pin "7") (pinfunction "7_7") (pintype "passive"))
      (node (ref "J31") (pin "9") (pinfunction "9_9") (pintype "passive"))
      (node (ref "J32") (pin "PAD1") (pinfunction "PAD1_PAD1") (pintype "bidirectional"))
      (node (ref "J32") (pin "PAD2") (pinfunction "PAD2_PAD2") (pintype "bidirectional"))
      (node (ref "J33") (pin "1") (pinfunction "1_1") (pintype "passive"))
      (node (ref "J33") (pin "10") (pinfunction "1_10") (pintype "passive"))
      (node (ref "J34") (pin "1") (pinfunction "1_1") (pintype "passive"))
      (node (ref "J34") (pin "11") (pinfunction "11_11") (pintype "passive"))
      (node (ref "J34") (pin "13") (pinfunction "13_13") (pintype "passive"))
      (node (ref "J34") (pin "15") (pinfunction "15_15") (pintype "passive"))
      (node (ref "J34") (pin "3") (pinfunction "3_3") (pintype "passive"))
      (node (ref "J34") (pin "5") (pinfunction "5_5") (pintype "passive"))
      (node (ref "J34") (pin "7") (pinfunction "7_7") (pintype "passive"))
      (node (ref "J34") (pin "9") (pinfunction "9_9") (pintype "passive"))
      (node (ref "J35") (pin "1") (pinfunction "1_1") (pintype "passive"))
      (node (ref "J35") (pin "10") (pinfunction "1_10") (pintype "passive"))
      (node (ref "J4") (pin "GND$1") (pinfunction "2_GND$1") (pintype "passive"))
      (node (ref "J4") (pin "GND$2") (pinfunction "2_GND$2") (pintype "passive"))
      (node (ref "J4") (pin "GND$3") (pinfunction "2_GND$3") (pintype "passive"))
      (node (ref "J4") (pin "GND$4") (pinfunction "2_GND$4") (pintype "passive"))
      (node (ref "J5") (pin "GND@1") (pinfunction "2_GND@1") (pintype "passive"))
      (node (ref "J5") (pin "GND@2") (pinfunction "2_GND@2") (pintype "passive"))
      (node (ref "J5") (pin "GND@3") (pinfunction "2_GND@3") (pintype "passive"))
      (node (ref "J5") (pin "GND@4") (pinfunction "2_GND@4") (pintype "passive"))
      (node (ref "J6") (pin "GND@1") (pinfunction "2_GND@1") (pintype "passive"))
      (node (ref "J6") (pin "GND@2") (pinfunction "2_GND@2") (pintype "passive"))
      (node (ref "J6") (pin "GND@3") (pinfunction "2_GND@3") (pintype "passive"))
      (node (ref "J6") (pin "GND@4") (pinfunction "2_GND@4") (pintype "passive"))
      (node (ref "J7") (pin "GND@1") (pinfunction "2_GND@1") (pintype "passive"))
      (node (ref "J7") (pin "GND@2") (pinfunction "2_GND@2") (pintype "passive"))
      (node (ref "J7") (pin "GND@3") (pinfunction "2_GND@3") (pintype "passive"))
      (node (ref "J7") (pin "GND@4") (pinfunction "2_GND@4") (pintype "passive"))
      (node (ref "J8") (pin "GND@1") (pinfunction "2_GND@1") (pintype "passive"))
      (node (ref "J8") (pin "GND@2") (pinfunction "2_GND@2") (pintype "passive"))
      (node (ref "J8") (pin "GND@3") (pinfunction "2_GND@3") (pintype "passive"))
      (node (ref "J8") (pin "GND@4") (pinfunction "2_GND@4") (pintype "passive"))
      (node (ref "Q5") (pin "2") (pinfunction "S_2") (pintype "bidirectional"))
      (node (ref "Q6") (pin "2") (pinfunction "S_2") (pintype "bidirectional"))
      (node (ref "Q7") (pin "2") (pinfunction "S_2") (pintype "bidirectional"))
      (node (ref "Q8") (pin "2") (pinfunction "S_2") (pintype "bidirectional"))
      (node (ref "R10") (pin "2") (pinfunction "2_2") (pintype "passive"))
      (node (ref "R11") (pin "1") (pinfunction "1_1") (pintype "passive"))
      (node (ref "R12") (pin "1") (pinfunction "1_1") (pintype "passive"))
      (node (ref "R13") (pin "1") (pinfunction "1_1") (pintype "passive"))
      (node (ref "R14") (pin "1") (pinfunction "1_1") (pintype "passive"))
      (node (ref "R15") (pin "1") (pinfunction "1_1") (pintype "passive"))
      (node (ref "R16") (pin "1") (pinfunction "1_1") (pintype "passive"))
      (node (ref "R17") (pin "1") (pinfunction "1_1") (pintype "passive"))
      (node (ref "R18") (pin "1") (pinfunction "1_1") (pintype "passive"))
      (node (ref "R19") (pin "2") (pinfunction "2_2") (pintype "passive"))
      (node (ref "R20") (pin "2") (pinfunction "2_2") (pintype "passive"))
      (node (ref "R21") (pin "2") (pinfunction "2_2") (pintype "passive"))
      (node (ref "R7") (pin "2") (pinfunction "2_2") (pintype "passive"))
      (node (ref "R8") (pin "2") (pinfunction "2_2") (pintype "passive"))
      (node (ref "R9") (pin "2") (pinfunction "2_2") (pintype "passive"))
      (node (ref "S1") (pin "2") (pinfunction "1_2") (pintype "passive"))
      (node (ref "S10") (pin "SW2") (pinfunction "S_SW2") (pintype "passive"))
      (node (ref "S2") (pin "2") (pinfunction "1_2") (pintype "passive"))
      (node (ref "S3") (pin "2") (pinfunction "1_2") (pintype "passive"))
      (node (ref "S4") (pin "2") (pinfunction "1_2") (pintype "passive"))
      (node (ref "S5") (pin "SW2") (pinfunction "S_SW2") (pintype "passive"))
      (node (ref "S6") (pin "SW2") (pinfunction "S_SW2") (pintype "passive"))
      (node (ref "S7") (pin "SW2") (pinfunction "S_SW2") (pintype "passive"))
      (node (ref "S8") (pin "SW2") (pinfunction "S_SW2") (pintype "passive"))
      (node (ref "S9") (pin "SW2") (pinfunction "S_SW2") (pintype "passive"))
      (node (ref "TP3") (pin "1") (pinfunction "TP_1") (pintype "bidirectional"))
      (node (ref "TP4") (pin "1") (pinfunction "TP_1") (pintype "bidirectional"))
      (node (ref "TP5") (pin "1") (pinfunction "TP_1") (pintype "bidirectional"))
      (node (ref "U1") (pin "4") (pinfunction "GND_4") (pintype "power_in"))
      (node (ref "U10") (pin "2") (pinfunction "GND_2") (pintype "power_in"))
      (node (ref "U11") (pin "4") (pinfunction "GND_4") (pintype "power_in"))
      (node (ref "U12") (pin "4") (pinfunction "GND_4") (pintype "power_in"))
      (node (ref "U13") (pin "4") (pinfunction "GND_4") (pintype "power_in"))
      (node (ref "U14") (pin "4") (pinfunction "GND_4") (pintype "power_in"))
      (node (ref "U15") (pin "4") (pinfunction "GND_4") (pintype "power_in"))
      (node (ref "U16") (pin "4") (pinfunction "GND_4") (pintype "power_in"))
      (node (ref "U17") (pin "4") (pinfunction "GND_4") (pintype "power_in"))
      (node (ref "U18") (pin "4") (pinfunction "GND_4") (pintype "power_in"))
      (node (ref "U19") (pin "4") (pinfunction "GND_4") (pintype "power_in"))
      (node (ref "U2") (pin "4") (pinfunction "GND_4") (pintype "power_in"))
      (node (ref "U20") (pin "4") (pinfunction "GND_4") (pintype "power_in"))
      (node (ref "U21") (pin "4") (pinfunction "GND_4") (pintype "power_in"))
      (node (ref "U22") (pin "4") (pinfunction "GND_4") (pintype "power_in"))
      (node (ref "U23") (pin "4") (pinfunction "GND_4") (pintype "power_in"))
      (node (ref "U24") (pin "4") (pinfunction "GND_4") (pintype "power_in"))
      (node (ref "U25") (pin "4") (pinfunction "GND_4") (pintype "power_in"))
      (node (ref "U26") (pin "4") (pinfunction "GND_4") (pintype "power_in"))
      (node (ref "U27") (pin "4") (pinfunction "GND_4") (pintype "power_in"))
      (node (ref "U28") (pin "4") (pinfunction "GND_4") (pintype "power_in"))
      (node (ref "U29") (pin "4") (pinfunction "GND_4") (pintype "power_in"))
      (node (ref "U3") (pin "4") (pinfunction "GND_4") (pintype "power_in"))
      (node (ref "U30") (pin "4") (pinfunction "GND_4") (pintype "power_in"))
      (node (ref "U31") (pin "4") (pinfunction "GND_4") (pintype "power_in"))
      (node (ref "U32") (pin "4") (pinfunction "GND_4") (pintype "power_in"))
      (node (ref "U33") (pin "4") (pinfunction "GND_4") (pintype "power_in"))
      (node (ref "U34") (pin "4") (pinfunction "GND_4") (pintype "power_in"))
      (node (ref "U35") (pin "4") (pinfunction "GND_4") (pintype "power_in"))
      (node (ref "U36") (pin "4") (pinfunction "GND_4") (pintype "power_in"))
      (node (ref "U37") (pin "4") (pinfunction "GND_4") (pintype "power_in"))
      (node (ref "U38") (pin "4") (pinfunction "GND_4") (pintype "power_in"))
      (node (ref "U39") (pin "4") (pinfunction "GND_4") (pintype "power_in"))
      (node (ref "U4") (pin "4") (pinfunction "GND_4") (pintype "power_in"))
      (node (ref "U40") (pin "4") (pinfunction "GND_4") (pintype "power_in"))
      (node (ref "U41") (pin "4") (pinfunction "GND_4") (pintype "power_in"))
      (node (ref "U42") (pin "4") (pinfunction "GND_4") (pintype "power_in"))
      (node (ref "U43") (pin "CASE1") (pinfunction "CASE_CASE1") (pintype "bidirectional"))
      (node (ref "U43") (pin "CASE2") (pinfunction "CASE_CASE2") (pintype "bidirectional"))
      (node (ref "U44") (pin "CASE1") (pinfunction "CASE_CASE1") (pintype "bidirectional"))
      (node (ref "U44") (pin "CASE2") (pinfunction "CASE_CASE2") (pintype "bidirectional"))
      (node (ref "U45") (pin "CASE1") (pinfunction "CASE_CASE1") (pintype "bidirectional"))
      (node (ref "U45") (pin "CASE2") (pinfunction "CASE_CASE2") (pintype "bidirectional"))
      (node (ref "U46") (pin "CASE1") (pinfunction "CASE_CASE1") (pintype "bidirectional"))
      (node (ref "U46") (pin "CASE2") (pinfunction "CASE_CASE2") (pintype "bidirectional"))
      (node (ref "U47") (pin "B5") (pinfunction "GND_B5") (pintype "power_in"))
      (node (ref "U47") (pin "C1") (pinfunction "GND_C1") (pintype "power_in"))
      (node (ref "U47") (pin "C2") (pinfunction "GND_C2") (pintype "power_in"))
      (node (ref "U47") (pin "C5") (pinfunction "SYNC/MODE_C5") (pintype "input"))
      (node (ref "U47") (pin "D5") (pinfunction "GND_D5") (pintype "power_in"))
      (node (ref "U48") (pin "4") (pinfunction "AGND_4") (pintype "bidirectional"))
      (node (ref "U49") (pin "GND@1") (pinfunction "GND_GND@1") (pintype "power_in"))
      (node (ref "U49") (pin "GND@2") (pinfunction "GND_GND@2") (pintype "power_in"))
      (node (ref "U5") (pin "4") (pinfunction "GND_4") (pintype "power_in"))
      (node (ref "U50") (pin "12") (pinfunction "GND_12") (pintype "bidirectional"))
      (node (ref "U50") (pin "2") (pinfunction "A1_2") (pintype "bidirectional"))
      (node (ref "U50") (pin "21") (pinfunction "A0_21") (pintype "bidirectional"))
      (node (ref "U50") (pin "3") (pinfunction "A2_3") (pintype "bidirectional"))
      (node (ref "U51") (pin "10") (pinfunction "C+_10") (pintype "input"))
      (node (ref "U51") (pin "12") (pinfunction "~{EN}_12") (pintype "input"))
      (node (ref "U51") (pin "14") (pinfunction "D+_14") (pintype "input"))
      (node (ref "U51") (pin "15") (pinfunction "D-_15") (pintype "input"))
      (node (ref "U51") (pin "8") (pinfunction "GND_8") (pintype "power_in"))
      (node (ref "U51") (pin "9") (pinfunction "C-_9") (pintype "input"))
      (node (ref "U52") (pin "4") (pinfunction "GND_4") (pintype "power_in"))
      (node (ref "U52") (pin "PAD") (pinfunction "GND_PAD") (pintype "power_in"))
      (node (ref "U53") (pin "3") (pinfunction "BIN_3") (pintype "input"))
      (node (ref "U53") (pin "4") (pinfunction "GND_4") (pintype "power_in"))
      (node (ref "U53") (pin "PAD") (pinfunction "GND_PAD") (pintype "power_in"))
      (node (ref "U6") (pin "4") (pinfunction "GND_4") (pintype "power_in"))
      (node (ref "U7") (pin "4") (pinfunction "GND_4") (pintype "power_in"))
      (node (ref "U8") (pin "4") (pinfunction "GND_4") (pintype "power_in"))
      (node (ref "U9") (pin "4") (pinfunction "GND_4") (pintype "power_in"))
    )
    (net (code "68") (name "HARP_CLKOUT") (class "Default")
      (node (ref "U48") (pin "2") (pinfunction "A1_2") (pintype "bidirectional"))
      (node (ref "U49") (pin "24") (pinfunction "24_24") (pintype "bidirectional"))
    )
    (net (code "69") (name "I2C_SCL") (class "Default")
      (node (ref "R23") (pin "2") (pinfunction "2_2") (pintype "passive"))
      (node (ref "U49") (pin "23") (pinfunction "23_23") (pintype "bidirectional"))
      (node (ref "U50") (pin "22") (pinfunction "SCL_22") (pintype "bidirectional"))
    )
    (net (code "70") (name "I2C_SDA") (class "Default")
      (node (ref "R24") (pin "2") (pinfunction "2_2") (pintype "passive"))
      (node (ref "U49") (pin "22") (pinfunction "22_22") (pintype "bidirectional"))
      (node (ref "U50") (pin "23") (pinfunction "SDA_23") (pintype "bidirectional"))
    )
    (net (code "71") (name "LVDS_IN_0") (class "Default")
      (node (ref "U49") (pin "18") (pinfunction "18_18") (pintype "bidirectional"))
      (node (ref "U51") (pin "3") (pinfunction "AOUT_3") (pintype "output"))
    )
    (net (code "72") (name "LVDS_IN_1") (class "Default")
      (node (ref "U49") (pin "17") (pinfunction "17_17") (pintype "bidirectional"))
      (node (ref "U51") (pin "5") (pinfunction "BOUT_5") (pintype "output"))
    )
    (net (code "73") (name "LVDS_OUT_0") (class "Default")
      (node (ref "U49") (pin "19") (pinfunction "19_19") (pintype "bidirectional"))
      (node (ref "U52") (pin "3") (pinfunction "BIN_3") (pintype "input"))
    )
    (net (code "74") (name "LVDS_OUT_1") (class "Default")
      (node (ref "U49") (pin "20") (pinfunction "20_20") (pintype "bidirectional"))
      (node (ref "U52") (pin "2") (pinfunction "AIN_2") (pintype "input"))
    )
    (net (code "75") (name "LVDS_OUT_2") (class "Default")
      (node (ref "U49") (pin "21") (pinfunction "21_21") (pintype "bidirectional"))
      (node (ref "U53") (pin "2") (pinfunction "AIN_2") (pintype "input"))
    )
    (net (code "76") (name "NEOPIXEL_DIN") (class "Default")
      (node (ref "J30") (pin "1") (pinfunction "1_1") (pintype "passive"))
      (node (ref "U10") (pin "3") (pinfunction "A_3") (pintype "bidirectional"))
    )
    (net (code "77") (name "Net-(C32-Pad1)") (class "Default")
      (node (ref "C32") (pin "1") (pinfunction "1_1") (pintype "passive"))
      (node (ref "R7") (pin "1") (pinfunction "1_1") (pintype "passive"))
    )
    (net (code "78") (name "Net-(C33-Pad1)") (class "Default")
      (node (ref "C33") (pin "1") (pinfunction "1_1") (pintype "passive"))
      (node (ref "R8") (pin "1") (pinfunction "1_1") (pintype "passive"))
    )
    (net (code "79") (name "Net-(C34-Pad1)") (class "Default")
      (node (ref "C34") (pin "1") (pinfunction "1_1") (pintype "passive"))
      (node (ref "R9") (pin "1") (pinfunction "1_1") (pintype "passive"))
    )
    (net (code "80") (name "Net-(C35-Pad1)") (class "Default")
      (node (ref "C35") (pin "1") (pinfunction "1_1") (pintype "passive"))
      (node (ref "R10") (pin "1") (pinfunction "1_1") (pintype "passive"))
    )
    (net (code "81") (name "Net-(J1-1)") (class "Default")
      (node (ref "J1") (pin "CLK") (pinfunction "1_CLK") (pintype "passive"))
      (node (ref "U43") (pin "1X6") (pinfunction "COM_A_1X6") (pintype "bidirectional"))
    )
    (net (code "82") (name "Net-(J2-1)") (class "Default")
      (node (ref "J2") (pin "CLK") (pinfunction "1_CLK") (pintype "passive"))
      (node (ref "U44") (pin "1X6") (pinfunction "COM_A_1X6") (pintype "bidirectional"))
    )
    (net (code "83") (name "Net-(J3-1)") (class "Default")
      (node (ref "J3") (pin "CLK") (pinfunction "1_CLK") (pintype "passive"))
      (node (ref "U45") (pin "1X6") (pinfunction "COM_A_1X6") (pintype "bidirectional"))
    )
    (net (code "84") (name "Net-(J4-1)") (class "Default")
      (node (ref "J4") (pin "CLK") (pinfunction "1_CLK") (pintype "passive"))
      (node (ref "U46") (pin "1X6") (pinfunction "COM_A_1X6") (pintype "bidirectional"))
    )
    (net (code "85") (name "Net-(J5-1)") (class "Default")
      (node (ref "J5") (pin "SIG") (pinfunction "1_SIG") (pintype "passive"))
      (node (ref "U43") (pin "5") (pinfunction "NO_A_5") (pintype "bidirectional"))
    )
    (net (code "86") (name "Net-(J6-1)") (class "Default")
      (node (ref "J6") (pin "SIG") (pinfunction "1_SIG") (pintype "passive"))
      (node (ref "U44") (pin "5") (pinfunction "NO_A_5") (pintype "bidirectional"))
    )
    (net (code "87") (name "Net-(J7-1)") (class "Default")
      (node (ref "J7") (pin "SIG") (pinfunction "1_SIG") (pintype "passive"))
      (node (ref "U45") (pin "5") (pinfunction "NO_A_5") (pintype "bidirectional"))
    )
    (net (code "88") (name "Net-(J8-1)") (class "Default")
      (node (ref "J8") (pin "SIG") (pinfunction "1_SIG") (pintype "passive"))
      (node (ref "U46") (pin "5") (pinfunction "NO_A_5") (pintype "bidirectional"))
    )
    (net (code "89") (name "Net-(J15-1)") (class "Default")
      (node (ref "J15") (pin "SIG") (pinfunction "1_SIG") (pintype "passive"))
      (node (ref "J16") (pin "CLK") (pinfunction "1_CLK") (pintype "passive"))
    )
    (net (code "90") (name "Net-(J18-1)") (class "Default")
      (node (ref "J18") (pin "SIG") (pinfunction "1_SIG") (pintype "passive"))
      (node (ref "J19") (pin "CLK") (pinfunction "1_CLK") (pintype "passive"))
    )
    (net (code "91") (name "Net-(J27-1)") (class "Default")
      (node (ref "J27") (pin "SIG") (pinfunction "1_SIG") (pintype "passive"))
      (node (ref "J28") (pin "CLK") (pinfunction "1_CLK") (pintype "passive"))
    )
    (net (code "92") (name "Net-(Q1-D)") (class "Default")
      (node (ref "D1") (pin "A") (pinfunction "A_A") (pintype "passive"))
      (node (ref "Q1") (pin "3") (pinfunction "D_3") (pintype "bidirectional"))
      (node (ref "U43") (pin "7") (pinfunction "COIL-_7") (pintype "bidirectional"))
    )
    (net (code "93") (name "Net-(Q1-S)") (class "Default")
      (node (ref "Q1") (pin "2") (pinfunction "S_2") (pintype "bidirectional"))
      (node (ref "Q5") (pin "3") (pinfunction "D_3") (pintype "bidirectional"))
    )
    (net (code "94") (name "Net-(Q2-D)") (class "Default")
      (node (ref "D2") (pin "A") (pinfunction "A_A") (pintype "passive"))
      (node (ref "Q2") (pin "3") (pinfunction "D_3") (pintype "bidirectional"))
      (node (ref "U44") (pin "7") (pinfunction "COIL-_7") (pintype "bidirectional"))
    )
    (net (code "95") (name "Net-(Q2-S)") (class "Default")
      (node (ref "Q2") (pin "2") (pinfunction "S_2") (pintype "bidirectional"))
      (node (ref "Q6") (pin "3") (pinfunction "D_3") (pintype "bidirectional"))
    )
    (net (code "96") (name "Net-(Q3-D)") (class "Default")
      (node (ref "D3") (pin "A") (pinfunction "A_A") (pintype "passive"))
      (node (ref "Q3") (pin "3") (pinfunction "D_3") (pintype "bidirectional"))
      (node (ref "U45") (pin "7") (pinfunction "COIL-_7") (pintype "bidirectional"))
    )
    (net (code "97") (name "Net-(Q3-S)") (class "Default")
      (node (ref "Q3") (pin "2") (pinfunction "S_2") (pintype "bidirectional"))
      (node (ref "Q7") (pin "3") (pinfunction "D_3") (pintype "bidirectional"))
    )
    (net (code "98") (name "Net-(Q4-D)") (class "Default")
      (node (ref "D4") (pin "A") (pinfunction "A_A") (pintype "passive"))
      (node (ref "Q4") (pin "3") (pinfunction "D_3") (pintype "bidirectional"))
      (node (ref "U46") (pin "7") (pinfunction "COIL-_7") (pintype "bidirectional"))
    )
    (net (code "99") (name "Net-(Q4-S)") (class "Default")
      (node (ref "Q4") (pin "2") (pinfunction "S_2") (pintype "bidirectional"))
      (node (ref "Q8") (pin "3") (pinfunction "D_3") (pintype "bidirectional"))
    )
    (net (code "100") (name "Net-(S1-2)") (class "Default")
      (node (ref "R3") (pin "1") (pinfunction "1_1") (pintype "passive"))
      (node (ref "S1") (pin "1") (pinfunction "2_1") (pintype "passive"))
    )
    (net (code "101") (name "Net-(S2-2)") (class "Default")
      (node (ref "R4") (pin "2") (pinfunction "2_2") (pintype "passive"))
      (node (ref "S2") (pin "1") (pinfunction "2_1") (pintype "passive"))
    )
    (net (code "102") (name "Net-(S3-2)") (class "Default")
      (node (ref "R5") (pin "2") (pinfunction "2_2") (pintype "passive"))
      (node (ref "S3") (pin "1") (pinfunction "2_1") (pintype "passive"))
    )
    (net (code "103") (name "Net-(S4-2)") (class "Default")
      (node (ref "R6") (pin "2") (pinfunction "2_2") (pintype "passive"))
      (node (ref "S4") (pin "1") (pinfunction "2_1") (pintype "passive"))
    )
    (net (code "104") (name "Net-(U1-DIN)") (class "Default")
      (node (ref "R1") (pin "2") (pinfunction "2_2") (pintype "passive"))
      (node (ref "U1") (pin "1") (pinfunction "DIN_1") (pintype "input"))
    )
    (net (code "105") (name "Net-(U1-DOUT)") (class "Default")
      (node (ref "U1") (pin "3") (pinfunction "DOUT_3") (pintype "output"))
      (node (ref "U2") (pin "1") (pinfunction "DIN_1") (pintype "input"))
    )
    (net (code "106") (name "Net-(U2-DOUT)") (class "Default")
      (node (ref "U2") (pin "3") (pinfunction "DOUT_3") (pintype "output"))
      (node (ref "U3") (pin "1") (pinfunction "DIN_1") (pintype "input"))
    )
    (net (code "107") (name "Net-(U3-DOUT)") (class "Default")
      (node (ref "U3") (pin "3") (pinfunction "DOUT_3") (pintype "output"))
      (node (ref "U4") (pin "1") (pinfunction "DIN_1") (pintype "input"))
    )
    (net (code "108") (name "Net-(U4-DOUT)") (class "Default")
      (node (ref "U4") (pin "3") (pinfunction "DOUT_3") (pintype "output"))
      (node (ref "U5") (pin "1") (pinfunction "DIN_1") (pintype "input"))
    )
    (net (code "109") (name "Net-(U5-DOUT)") (class "Default")
      (node (ref "U5") (pin "3") (pinfunction "DOUT_3") (pintype "output"))
      (node (ref "U6") (pin "1") (pinfunction "DIN_1") (pintype "input"))
    )
    (net (code "110") (name "Net-(U6-DOUT)") (class "Default")
      (node (ref "U6") (pin "3") (pinfunction "DOUT_3") (pintype "output"))
      (node (ref "U7") (pin "1") (pinfunction "DIN_1") (pintype "input"))
    )
    (net (code "111") (name "Net-(U7-DOUT)") (class "Default")
      (node (ref "U7") (pin "3") (pinfunction "DOUT_3") (pintype "output"))
      (node (ref "U8") (pin "1") (pinfunction "DIN_1") (pintype "input"))
    )
    (net (code "112") (name "Net-(U8-DOUT)") (class "Default")
      (node (ref "U8") (pin "3") (pinfunction "DOUT_3") (pintype "output"))
      (node (ref "U9") (pin "1") (pinfunction "DIN_1") (pintype "input"))
    )
    (net (code "113") (name "Net-(U10-B)") (class "Default")
      (node (ref "R1") (pin "1") (pinfunction "1_1") (pintype "passive"))
      (node (ref "U10") (pin "4") (pinfunction "B_4") (pintype "bidirectional"))
    )
    (net (code "114") (name "Net-(U10-OE)") (class "Default")
      (node (ref "R2") (pin "2") (pinfunction "2_2") (pintype "passive"))
      (node (ref "U10") (pin "5") (pinfunction "OE_5") (pintype "bidirectional"))
    )
    (net (code "115") (name "Net-(U11-DIN)") (class "Default")
      (node (ref "U11") (pin "1") (pinfunction "DIN_1") (pintype "input"))
      (node (ref "U9") (pin "3") (pinfunction "DOUT_3") (pintype "output"))
    )
    (net (code "116") (name "Net-(U11-DOUT)") (class "Default")
      (node (ref "U11") (pin "3") (pinfunction "DOUT_3") (pintype "output"))
      (node (ref "U12") (pin "1") (pinfunction "DIN_1") (pintype "input"))
    )
    (net (code "117") (name "Net-(U12-DOUT)") (class "Default")
      (node (ref "U12") (pin "3") (pinfunction "DOUT_3") (pintype "output"))
      (node (ref "U13") (pin "1") (pinfunction "DIN_1") (pintype "input"))
    )
    (net (code "118") (name "Net-(U13-DOUT)") (class "Default")
      (node (ref "U13") (pin "3") (pinfunction "DOUT_3") (pintype "output"))
      (node (ref "U14") (pin "1") (pinfunction "DIN_1") (pintype "input"))
    )
    (net (code "119") (name "Net-(U14-DOUT)") (class "Default")
      (node (ref "U14") (pin "3") (pinfunction "DOUT_3") (pintype "output"))
      (node (ref "U15") (pin "1") (pinfunction "DIN_1") (pintype "input"))
    )
    (net (code "120") (name "Net-(U15-DOUT)") (class "Default")
      (node (ref "U15") (pin "3") (pinfunction "DOUT_3") (pintype "output"))
      (node (ref "U16") (pin "1") (pinfunction "DIN_1") (pintype "input"))
    )
    (net (code "121") (name "Net-(U16-DOUT)") (class "Default")
      (node (ref "U16") (pin "3") (pinfunction "DOUT_3") (pintype "output"))
      (node (ref "U17") (pin "1") (pinfunction "DIN_1") (pintype "input"))
    )
    (net (code "122") (name "Net-(U17-DOUT)") (class "Default")
      (node (ref "U17") (pin "3") (pinfunction "DOUT_3") (pintype "output"))
      (node (ref "U18") (pin "1") (pinfunction "DIN_1") (pintype "input"))
    )
    (net (code "123") (name "Net-(U18-DOUT)") (class "Default")
      (node (ref "U18") (pin "3") (pinfunction "DOUT_3") (pintype "output"))
      (node (ref "U19") (pin "1") (pinfunction "DIN_1") (pintype "input"))
    )
    (net (code "124") (name "Net-(U19-DOUT)") (class "Default")
      (node (ref "U19") (pin "3") (pinfunction "DOUT_3") (pintype "output"))
      (node (ref "U20") (pin "1") (pinfunction "DIN_1") (pintype "input"))
    )
    (net (code "125") (name "Net-(U20-DOUT)") (class "Default")
      (node (ref "U20") (pin "3") (pinfunction "DOUT_3") (pintype "output"))
      (node (ref "U21") (pin "1") (pinfunction "DIN_1") (pintype "input"))
    )
    (net (code "126") (name "Net-(U21-DOUT)") (class "Default")
      (node (ref "U21") (pin "3") (pinfunction "DOUT_3") (pintype "output"))
      (node (ref "U22") (pin "1") (pinfunction "DIN_1") (pintype "input"))
    )
    (net (code "127") (name "Net-(U22-DOUT)") (class "Default")
      (node (ref "U22") (pin "3") (pinfunction "DOUT_3") (pintype "output"))
      (node (ref "U23") (pin "1") (pinfunction "DIN_1") (pintype "input"))
    )
    (net (code "128") (name "Net-(U23-DOUT)") (class "Default")
      (node (ref "U23") (pin "3") (pinfunction "DOUT_3") (pintype "output"))
      (node (ref "U24") (pin "1") (pinfunction "DIN_1") (pintype "input"))
    )
    (net (code "129") (name "Net-(U24-DOUT)") (class "Default")
      (node (ref "U24") (pin "3") (pinfunction "DOUT_3") (pintype "output"))
      (node (ref "U25") (pin "1") (pinfunction "DIN_1") (pintype "input"))
    )
    (net (code "130") (name "Net-(U25-DOUT)") (class "Default")
      (node (ref "U25") (pin "3") (pinfunction "DOUT_3") (pintype "output"))
      (node (ref "U26") (pin "1") (pinfunction "DIN_1") (pintype "input"))
    )
    (net (code "131") (name "Net-(U26-DOUT)") (class "Default")
      (node (ref "U26") (pin "3") (pinfunction "DOUT_3") (pintype "output"))
      (node (ref "U27") (pin "1") (pinfunction "DIN_1") (pintype "input"))
    )
    (net (code "132") (name "Net-(U27-DOUT)") (class "Default")
      (node (ref "U27") (pin "3") (pinfunction "DOUT_3") (pintype "output"))
      (node (ref "U28") (pin "1") (pinfunction "DIN_1") (pintype "input"))
    )
    (net (code "133") (name "Net-(U28-DOUT)") (class "Default")
      (node (ref "U28") (pin "3") (pinfunction "DOUT_3") (pintype "output"))
      (node (ref "U29") (pin "1") (pinfunction "DIN_1") (pintype "input"))
    )
    (net (code "134") (name "Net-(U29-DOUT)") (class "Default")
      (node (ref "U29") (pin "3") (pinfunction "DOUT_3") (pintype "output"))
      (node (ref "U30") (pin "1") (pinfunction "DIN_1") (pintype "input"))
    )
    (net (code "135") (name "Net-(U30-DOUT)") (class "Default")
      (node (ref "U30") (pin "3") (pinfunction "DOUT_3") (pintype "output"))
      (node (ref "U31") (pin "1") (pinfunction "DIN_1") (pintype "input"))
    )
    (net (code "136") (name "Net-(U31-DOUT)") (class "Default")
      (node (ref "U31") (pin "3") (pinfunction "DOUT_3") (pintype "output"))
      (node (ref "U32") (pin "1") (pinfunction "DIN_1") (pintype "input"))
    )
    (net (code "137") (name "Net-(U32-DOUT)") (class "Default")
      (node (ref "U32") (pin "3") (pinfunction "DOUT_3") (pintype "output"))
      (node (ref "U33") (pin "1") (pinfunction "DIN_1") (pintype "input"))
    )
    (net (code "138") (name "Net-(U33-DOUT)") (class "Default")
      (node (ref "U33") (pin "3") (pinfunction "DOUT_3") (pintype "output"))
      (node (ref "U34") (pin "1") (pinfunction "DIN_1") (pintype "input"))
    )
    (net (code "139") (name "Net-(U34-DOUT)") (class "Default")
      (node (ref "U34") (pin "3") (pinfunction "DOUT_3") (pintype "output"))
      (node (ref "U35") (pin "1") (pinfunction "DIN_1") (pintype "input"))
    )
    (net (code "140") (name "Net-(U35-DOUT)") (class "Default")
      (node (ref "U35") (pin "3") (pinfunction "DOUT_3") (pintype "output"))
      (node (ref "U36") (pin "1") (pinfunction "DIN_1") (pintype "input"))
    )
    (net (code "141") (name "Net-(U36-DOUT)") (class "Default")
      (node (ref "U36") (pin "3") (pinfunction "DOUT_3") (pintype "output"))
      (node (ref "U37") (pin "1") (pinfunction "DIN_1") (pintype "input"))
    )
    (net (code "142") (name "Net-(U37-DOUT)") (class "Default")
      (node (ref "U37") (pin "3") (pinfunction "DOUT_3") (pintype "output"))
      (node (ref "U38") (pin "1") (pinfunction "DIN_1") (pintype "input"))
    )
    (net (code "143") (name "Net-(U38-DOUT)") (class "Default")
      (node (ref "U38") (pin "3") (pinfunction "DOUT_3") (pintype "output"))
      (node (ref "U39") (pin "1") (pinfunction "DIN_1") (pintype "input"))
    )
    (net (code "144") (name "Net-(U39-DOUT)") (class "Default")
      (node (ref "U39") (pin "3") (pinfunction "DOUT_3") (pintype "output"))
      (node (ref "U40") (pin "1") (pinfunction "DIN_1") (pintype "input"))
    )
    (net (code "145") (name "Net-(U40-DOUT)") (class "Default")
      (node (ref "U40") (pin "3") (pinfunction "DOUT_3") (pintype "output"))
      (node (ref "U41") (pin "1") (pinfunction "DIN_1") (pintype "input"))
    )
    (net (code "146") (name "Net-(U41-DOUT)") (class "Default")
      (node (ref "U41") (pin "3") (pinfunction "DOUT_3") (pintype "output"))
      (node (ref "U42") (pin "1") (pinfunction "DIN_1") (pintype "input"))
    )
    (net (code "147") (name "Net-(U43-NC_A)") (class "Default")
      (node (ref "C32") (pin "2") (pinfunction "2_2") (pintype "passive"))
      (node (ref "U43") (pin "6") (pinfunction "NC_A_6") (pintype "bidirectional"))
    )
    (net (code "148") (name "Net-(U44-NC_A)") (class "Default")
      (node (ref "C33") (pin "2") (pinfunction "2_2") (pintype "passive"))
      (node (ref "U44") (pin "6") (pinfunction "NC_A_6") (pintype "bidirectional"))
    )
    (net (code "149") (name "Net-(U45-NC_A)") (class "Default")
      (node (ref "C34") (pin "2") (pinfunction "2_2") (pintype "passive"))
      (node (ref "U45") (pin "6") (pinfunction "NC_A_6") (pintype "bidirectional"))
    )
    (net (code "150") (name "Net-(U46-NC_A)") (class "Default")
      (node (ref "C35") (pin "2") (pinfunction "2_2") (pintype "passive"))
      (node (ref "U46") (pin "6") (pinfunction "NC_A_6") (pintype "bidirectional"))
    )
    (net (code "151") (name "Net-(U47-FB1)") (class "Default")
      (node (ref "R19") (pin "1") (pinfunction "1_1") (pintype "passive"))
      (node (ref "U47") (pin "E4") (pinfunction "FB1_E4") (pintype "input"))
    )
    (net (code "152") (name "Net-(U47-FB2)") (class "Default")
      (node (ref "R21") (pin "1") (pinfunction "1_1") (pintype "passive"))
      (node (ref "U47") (pin "A4") (pinfunction "FB2_A4") (pintype "input"))
    )
    (net (code "153") (name "Net-(U47-FREQ)") (class "Default")
      (node (ref "R20") (pin "1") (pinfunction "1_1") (pintype "passive"))
      (node (ref "U47") (pin "C4") (pinfunction "FREQ_C4") (pintype "input"))
    )
    (net (code "154") (name "Net-(U47-TRACK{slash}SS1)") (class "Default")
      (node (ref "C39") (pin "2") (pinfunction "2_2") (pintype "passive"))
      (node (ref "U47") (pin "E3") (pinfunction "TRACK/SS1_E3") (pintype "input"))
    )
    (net (code "155") (name "Net-(U47-TRACK{slash}SS2)") (class "Default")
      (node (ref "C38") (pin "2") (pinfunction "2_2") (pintype "passive"))
      (node (ref "U47") (pin "A3") (pinfunction "TRACK/SS2_A3") (pintype "input"))
    )
    (net (code "156") (name "Net-(U48-B1)") (class "Default")
      (node (ref "J29") (pin "4") (pinfunction "4_4") (pintype "passive"))
      (node (ref "U48") (pin "6") (pinfunction "B1_6") (pintype "bidirectional"))
    )
    (net (code "157") (name "Net-(U48-BGND)") (class "Default")
      (node (ref "C41") (pin "2") (pinfunction "2_2") (pintype "passive"))
      (node (ref "J29") (pin "5") (pinfunction "5_5") (pintype "passive"))
      (node (ref "U48") (pin "5") (pinfunction "BGND_5") (pintype "bidirectional"))
    )
    (net (code "158") (name "Net-(U48-BVDD)") (class "Default")
      (node (ref "C41") (pin "1") (pinfunction "1_1") (pintype "passive"))
      (node (ref "J29") (pin "1") (pinfunction "1_1") (pintype "passive"))
      (node (ref "U48") (pin "8") (pinfunction "BVDD_8") (pintype "bidirectional"))
    )
    (net (code "159") (name "RELAY_AND_0") (class "Default")
      (node (ref "Q5") (pin "1") (pinfunction "G_1") (pintype "bidirectional"))
      (node (ref "R11") (pin "2") (pinfunction "2_2") (pintype "passive"))
      (node (ref "U50") (pin "8") (pinfunction "P04_8") (pintype "bidirectional"))
    )
    (net (code "160") (name "RELAY_AND_1") (class "Default")
      (node (ref "Q6") (pin "1") (pinfunction "G_1") (pintype "bidirectional"))
      (node (ref "R13") (pin "2") (pinfunction "2_2") (pintype "passive"))
      (node (ref "U50") (pin "6") (pinfunction "P02_6") (pintype "bidirectional"))
    )
    (net (code "161") (name "RELAY_AND_2") (class "Default")
      (node (ref "Q7") (pin "1") (pinfunction "G_1") (pintype "bidirectional"))
      (node (ref "R15") (pin "2") (pinfunction "2_2") (pintype "passive"))
      (node (ref "U50") (pin "4") (pinfunction "P00_4") (pintype "bidirectional"))
    )
    (net (code "162") (name "RELAY_AND_3") (class "Default")
      (node (ref "Q8") (pin "1") (pinfunction "G_1") (pintype "bidirectional"))
      (node (ref "R17") (pin "2") (pinfunction "2_2") (pintype "passive"))
      (node (ref "U50") (pin "20") (pinfunction "P17_20") (pintype "bidirectional"))
    )
    (net (code "163") (name "RELAY_MECH_0") (class "Default")
      (node (ref "C28") (pin "2") (pinfunction "2_2") (pintype "passive"))
      (node (ref "Q1") (pin "1") (pinfunction "G_1") (pintype "bidirectional"))
      (node (ref "R12") (pin "2") (pinfunction "2_2") (pintype "passive"))
      (node (ref "R3") (pin "2") (pinfunction "2_2") (pintype "passive"))
      (node (ref "U50") (pin "9") (pinfunction "P05_9") (pintype "bidirectional"))
    )
    (net (code "164") (name "RELAY_MECH_1") (class "Default")
      (node (ref "C29") (pin "2") (pinfunction "2_2") (pintype "passive"))
      (node (ref "Q2") (pin "1") (pinfunction "G_1") (pintype "bidirectional"))
      (node (ref "R14") (pin "2") (pinfunction "2_2") (pintype "passive"))
      (node (ref "R4") (pin "1") (pinfunction "1_1") (pintype "passive"))
      (node (ref "U50") (pin "7") (pinfunction "P03_7") (pintype "bidirectional"))
    )
    (net (code "165") (name "RELAY_MECH_2") (class "Default")
      (node (ref "C30") (pin "2") (pinfunction "2_2") (pintype "passive"))
      (node (ref "Q3") (pin "1") (pinfunction "G_1") (pintype "bidirectional"))
      (node (ref "R16") (pin "2") (pinfunction "2_2") (pintype "passive"))
      (node (ref "R5") (pin "1") (pinfunction "1_1") (pintype "passive"))
      (node (ref "U50") (pin "5") (pinfunction "P01_5") (pintype "bidirectional"))
    )
    (net (code "166") (name "RELAY_MECH_3") (class "Default")
      (node (ref "C31") (pin "2") (pinfunction "2_2") (pintype "passive"))
      (node (ref "Q4") (pin "1") (pinfunction "G_1") (pintype "bidirectional"))
      (node (ref "R18") (pin "2") (pinfunction "2_2") (pintype "passive"))
      (node (ref "R6") (pin "1") (pinfunction "1_1") (pintype "passive"))
      (node (ref "U50") (pin "19") (pinfunction "P16_19") (pintype "bidirectional"))
    )
    (net (code "167") (name "unconnected-(U42-DOUT-Pad3)") (class "Default")
      (node (ref "U42") (pin "3") (pinfunction "DOUT_3") (pintype "output"))
    )
    (net (code "168") (name "unconnected-(U43-COM_B-Pad3)") (class "Default")
      (node (ref "U43") (pin "3") (pinfunction "COM_B_3") (pintype "bidirectional"))
    )
    (net (code "169") (name "unconnected-(U43-NC_B-Pad2)") (class "Default")
      (node (ref "U43") (pin "2") (pinfunction "NC_B_2") (pintype "bidirectional"))
    )
    (net (code "170") (name "unconnected-(U43-NO_B-Pad4)") (class "Default")
      (node (ref "U43") (pin "4") (pinfunction "NO_B_4") (pintype "bidirectional"))
    )
    (net (code "171") (name "unconnected-(U44-COM_B-Pad3)") (class "Default")
      (node (ref "U44") (pin "3") (pinfunction "COM_B_3") (pintype "bidirectional"))
    )
    (net (code "172") (name "unconnected-(U44-NC_B-Pad2)") (class "Default")
      (node (ref "U44") (pin "2") (pinfunction "NC_B_2") (pintype "bidirectional"))
    )
    (net (code "173") (name "unconnected-(U44-NO_B-Pad4)") (class "Default")
      (node (ref "U44") (pin "4") (pinfunction "NO_B_4") (pintype "bidirectional"))
    )
    (net (code "174") (name "unconnected-(U45-COM_B-Pad3)") (class "Default")
      (node (ref "U45") (pin "3") (pinfunction "COM_B_3") (pintype "bidirectional"))
    )
    (net (code "175") (name "unconnected-(U45-NC_B-Pad2)") (class "Default")
      (node (ref "U45") (pin "2") (pinfunction "NC_B_2") (pintype "bidirectional"))
    )
    (net (code "176") (name "unconnected-(U45-NO_B-Pad4)") (class "Default")
      (node (ref "U45") (pin "4") (pinfunction "NO_B_4") (pintype "bidirectional"))
    )
    (net (code "177") (name "unconnected-(U46-COM_B-Pad3)") (class "Default")
      (node (ref "U46") (pin "3") (pinfunction "COM_B_3") (pintype "bidirectional"))
    )
    (net (code "178") (name "unconnected-(U46-NC_B-Pad2)") (class "Default")
      (node (ref "U46") (pin "2") (pinfunction "NC_B_2") (pintype "bidirectional"))
    )
    (net (code "179") (name "unconnected-(U46-NO_B-Pad4)") (class "Default")
      (node (ref "U46") (pin "4") (pinfunction "NO_B_4") (pintype "bidirectional"))
    )
    (net (code "180") (name "unconnected-(U47-COMP1-PadE5)") (class "Default")
      (node (ref "U47") (pin "E5") (pinfunction "COMP1_E5") (pintype "bidirectional"))
    )
    (net (code "181") (name "unconnected-(U47-COMP2-PadA5)") (class "Default")
      (node (ref "U47") (pin "A5") (pinfunction "COMP2_A5") (pintype "bidirectional"))
    )
    (net (code "182") (name "unconnected-(U47-INTVCC-PadC3)") (class "Default")
      (node (ref "U47") (pin "C3") (pinfunction "INTVCC_C3") (pintype "output"))
    )
    (net (code "183") (name "unconnected-(U47-PGOOD1-PadD4)") (class "Default")
      (node (ref "U47") (pin "D4") (pinfunction "PGOOD1_D4") (pintype "open_collector"))
    )
    (net (code "184") (name "unconnected-(U47-PGOOD2-PadB4)") (class "Default")
      (node (ref "U47") (pin "B4") (pinfunction "PGOOD2_B4") (pintype "open_collector"))
    )
    (net (code "185") (name "unconnected-(U48-AVDD{slash}NC-Pad3)") (class "Default")
      (node (ref "U48") (pin "3") (pinfunction "AVDD/NC_3") (pintype "bidirectional"))
    )
    (net (code "186") (name "unconnected-(U48-BGND{slash}NC-Pad7)") (class "Default")
      (node (ref "U48") (pin "7") (pinfunction "BGND/NC_7") (pintype "bidirectional"))
    )
    (net (code "187") (name "unconnected-(U50-P10-Pad13)") (class "Default")
      (node (ref "U50") (pin "13") (pinfunction "P10_13") (pintype "bidirectional"))
    )
    (net (code "188") (name "unconnected-(U50-P12-Pad15)") (class "Default")
      (node (ref "U50") (pin "15") (pinfunction "P12_15") (pintype "bidirectional"))
    )
    (net (code "189") (name "unconnected-(U51-COUT-Pad11)") (class "Default")
      (node (ref "U51") (pin "11") (pinfunction "COUT_11") (pintype "output"))
    )
    (net (code "190") (name "unconnected-(U51-DOUT-Pad13)") (class "Default")
      (node (ref "U51") (pin "13") (pinfunction "DOUT_13") (pintype "output"))
    )
    (net (code "191") (name "unconnected-(U53-BOUT+-Pad6)") (class "Default")
      (node (ref "U53") (pin "6") (pinfunction "BOUT+_6") (pintype "output"))
    )
    (net (code "192") (name "unconnected-(U53-BOUT--Pad5)") (class "Default")
      (node (ref "U53") (pin "5") (pinfunction "BOUT-_5") (pintype "output"))
    )
  )
)
